# POVRotor.net
KiCad netlist of a schematic drawn in EAGLE
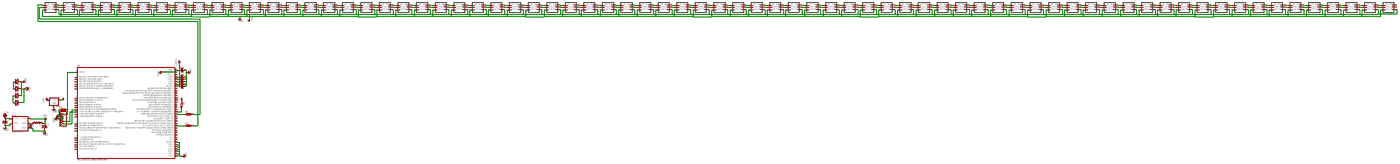
[diagram p0: schematic, sheet 1, overview]
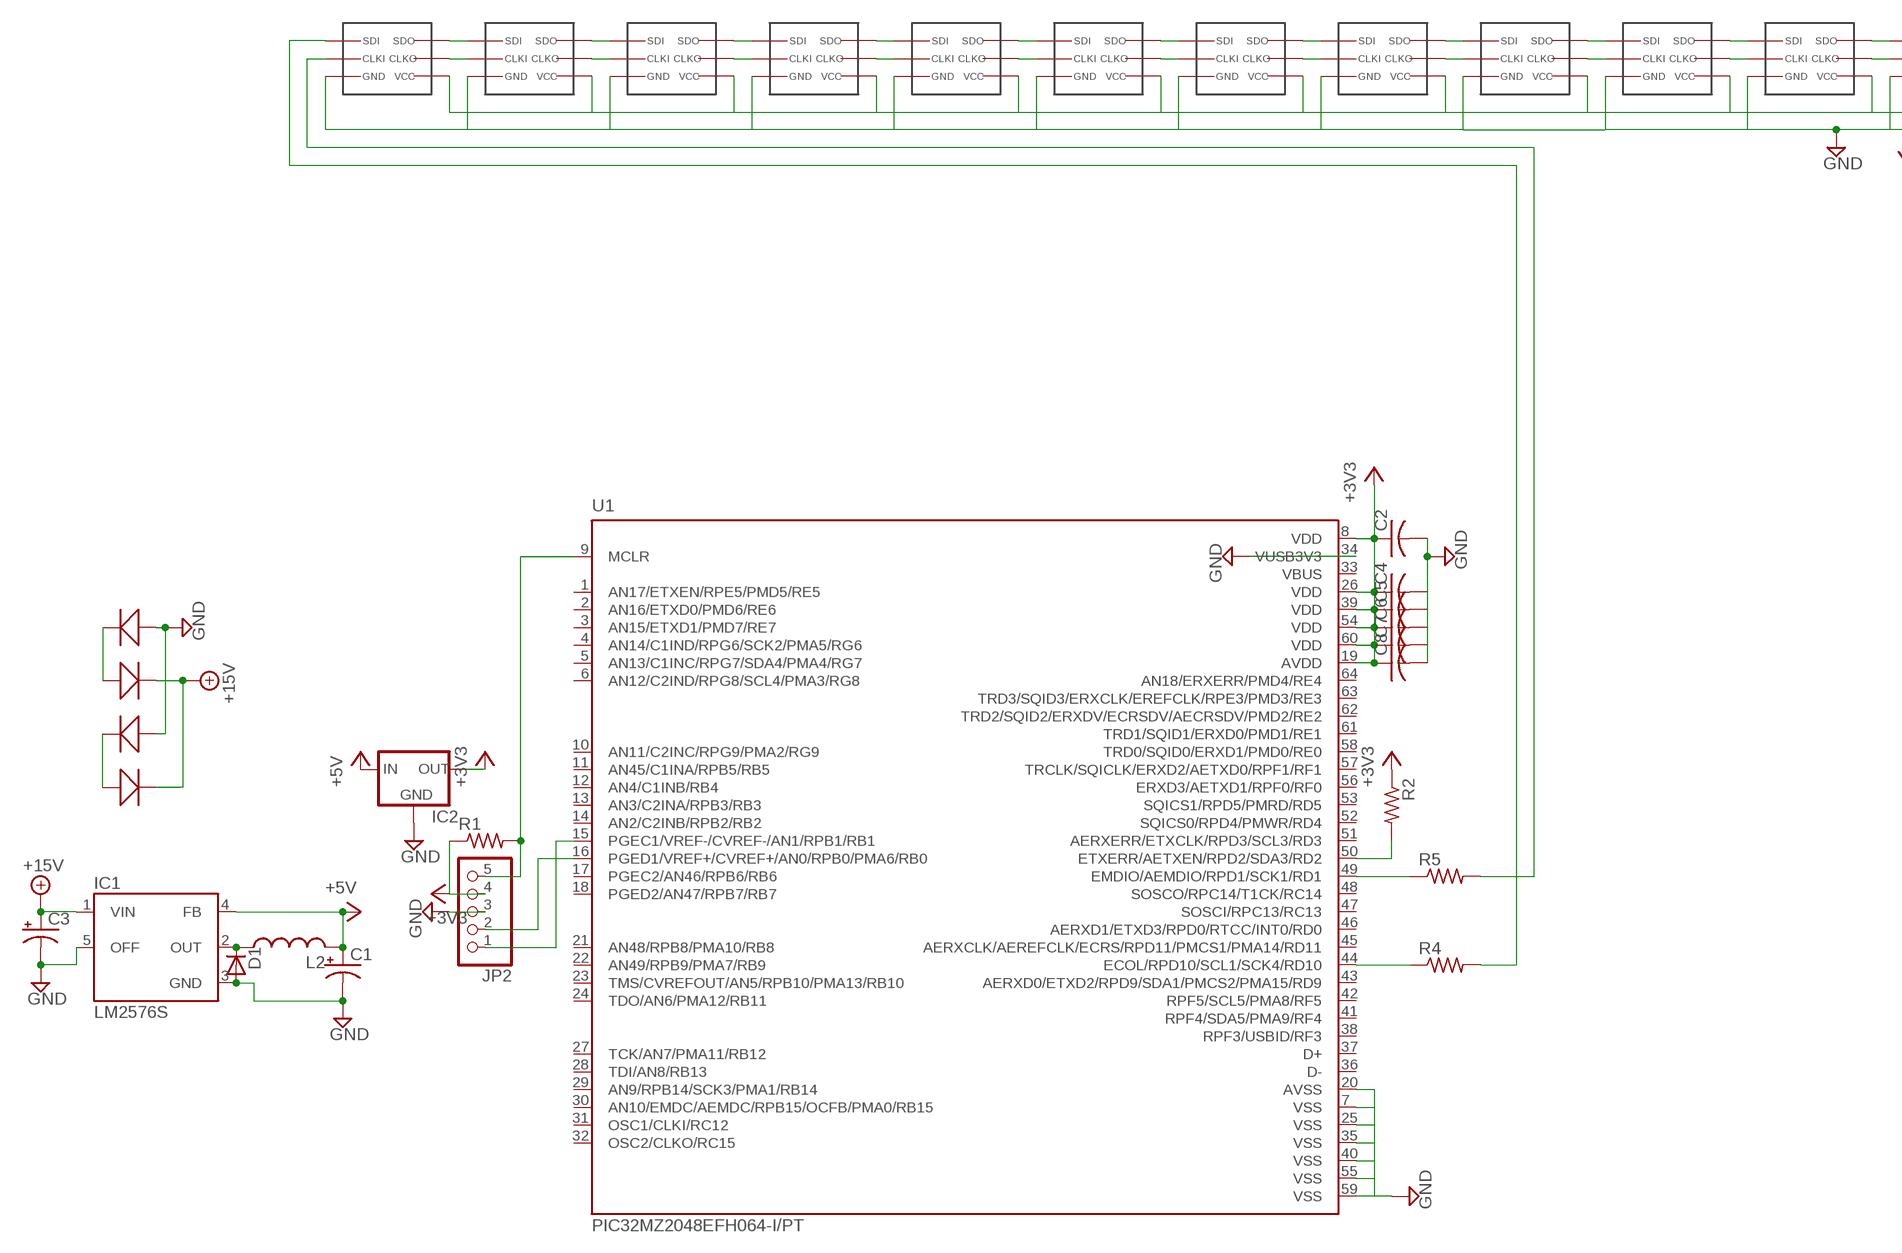
[diagram p1: schematic, sheet 1, part 1 of 8]
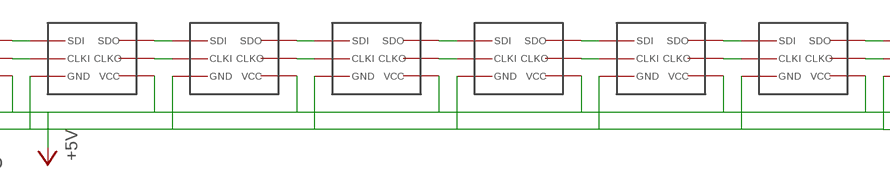
[diagram p2: schematic, sheet 1, part 2 of 8]
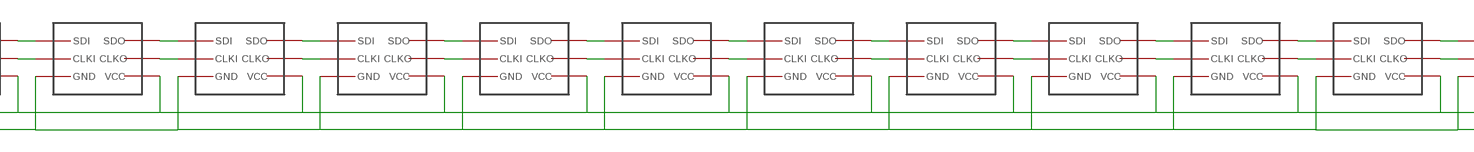
[diagram p3: schematic, sheet 1, part 3 of 8]
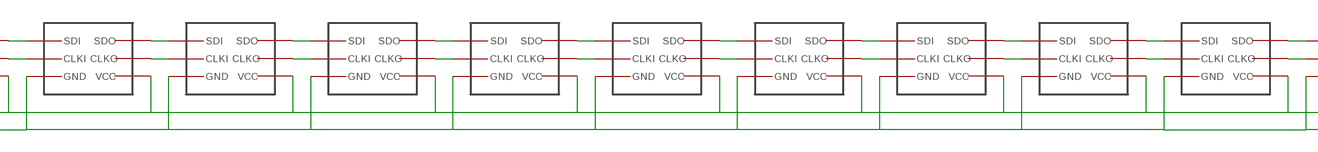
[diagram p4: schematic, sheet 1, part 4 of 8]
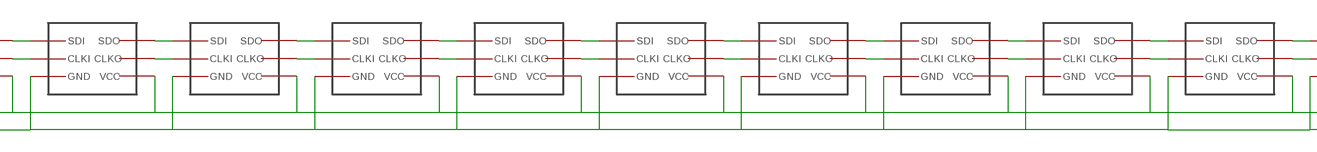
[diagram p5: schematic, sheet 1, part 5 of 8]
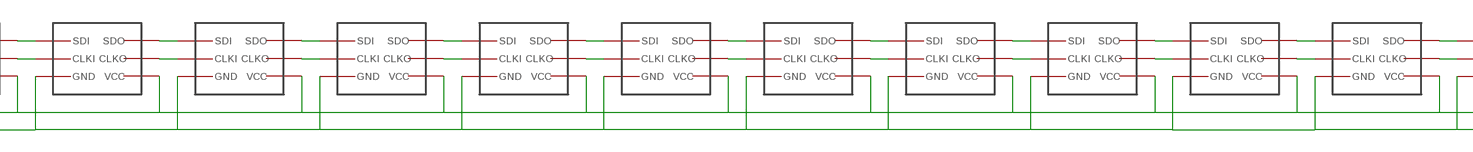
[diagram p6: schematic, sheet 1, part 6 of 8]
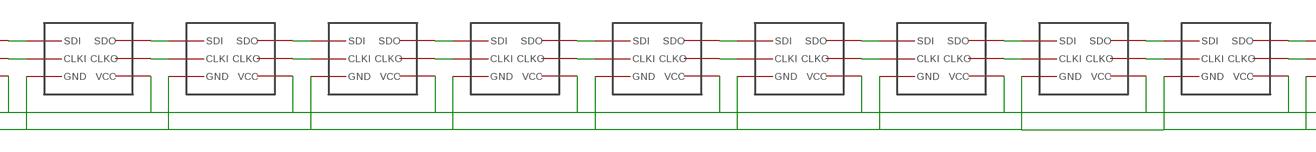
[diagram p7: schematic, sheet 1, part 7 of 8]
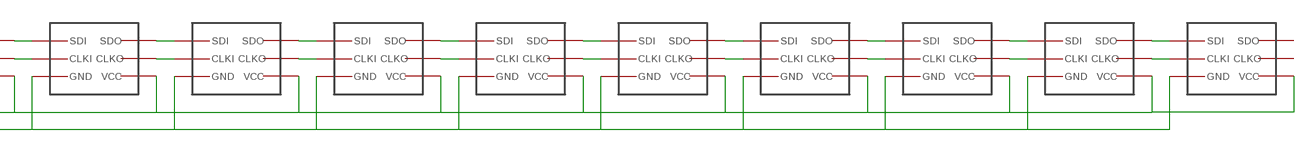
[diagram p8: schematic, sheet 1, part 8 of 8]

(export (version "E")
  (design (tool "Eeschema 10.0.6"))
  (components
    (comp (ref "C1")
      (value "CPOL-USE2,5-6E")
      (footprint "eagle-import:E2,5-6E")
      (libsource (lib "eagle-import") (part "CPOL-USE2,5-6E"))
    )
    (comp (ref "C2")
      (value "C-USC0805")
      (footprint "eagle-import:C0805")
      (libsource (lib "eagle-import") (part "C-USC0805"))
    )
    (comp (ref "C3")
      (value "CPOL-USE2,5-6E")
      (footprint "eagle-import:E2,5-6E")
      (libsource (lib "eagle-import") (part "CPOL-USE2,5-6E"))
    )
    (comp (ref "C4")
      (value "C-USC0805")
      (footprint "eagle-import:C0805")
      (libsource (lib "eagle-import") (part "C-USC0805"))
    )
    (comp (ref "C5")
      (value "C-USC0805")
      (footprint "eagle-import:C0805")
      (libsource (lib "eagle-import") (part "C-USC0805"))
    )
    (comp (ref "C6")
      (value "C-USC0805")
      (footprint "eagle-import:C0805")
      (libsource (lib "eagle-import") (part "C-USC0805"))
    )
    (comp (ref "C7")
      (value "C-USC0805")
      (footprint "eagle-import:C0805")
      (libsource (lib "eagle-import") (part "C-USC0805"))
    )
    (comp (ref "C8")
      (value "C-USC0805")
      (footprint "eagle-import:C0805")
      (libsource (lib "eagle-import") (part "C-USC0805"))
    )
    (comp (ref "D1")
      (value "BYS10")
      (footprint "eagle-import:SOD106A")
      (fields (field (name "MPN") "BYS10/45"))
      (libsource (lib "eagle-import") (part "BYS10"))
    )
    (comp (ref "D2")
      (value "SMD-DIODE-SCHOTTKY-40V-3A(DO-214AB)")
      (footprint "eagle-import:DO-214AB")
      (fields (field (name "MF") "Vishay") (field (name "MP") "SS34-E3/57T"))
      (libsource (lib "eagle-import") (part "SMD-DIODE-SCHOTTKY-40V-3A(DO-214AB)"))
    )
    (comp (ref "D3")
      (value "SMD-DIODE-SCHOTTKY-40V-3A(DO-214AB)")
      (footprint "eagle-import:DO-214AB")
      (fields (field (name "MF") "Vishay") (field (name "MP") "SS34-E3/57T"))
      (libsource (lib "eagle-import") (part "SMD-DIODE-SCHOTTKY-40V-3A(DO-214AB)"))
    )
    (comp (ref "D4")
      (value "SMD-DIODE-SCHOTTKY-40V-3A(DO-214AB)")
      (footprint "eagle-import:DO-214AB")
      (fields (field (name "MF") "Vishay") (field (name "MP") "SS34-E3/57T"))
      (libsource (lib "eagle-import") (part "SMD-DIODE-SCHOTTKY-40V-3A(DO-214AB)"))
    )
    (comp (ref "D5")
      (value "SMD-DIODE-SCHOTTKY-40V-3A(DO-214AB)")
      (footprint "eagle-import:DO-214AB")
      (fields (field (name "MF") "Vishay") (field (name "MP") "SS34-E3/57T"))
      (libsource (lib "eagle-import") (part "SMD-DIODE-SCHOTTKY-40V-3A(DO-214AB)"))
    )
    (comp (ref "IC1")
      (value "LM2576S")
      (footprint "eagle-import:TO263-5")
      (libsource (lib "eagle-import") (part "LM2576S"))
    )
    (comp (ref "IC2")
      (value "LM1117")
      (footprint "eagle-import:SOT223")
      (libsource (lib "eagle-import") (part "LM1117"))
    )
    (comp (ref "JP2")
      (value "PINHD-1X5")
      (footprint "eagle-import:1X05")
      (libsource (lib "eagle-import") (part "PINHD-1X5"))
    )
    (comp (ref "L2")
      (value "L-USL4532P")
      (footprint "eagle-import:L4532P")
      (libsource (lib "eagle-import") (part "L-USL4532P"))
    )
    (comp (ref "R1")
      (value "R-US_R0805")
      (footprint "eagle-import:R0805")
      (libsource (lib "eagle-import") (part "R-US_R0805"))
    )
    (comp (ref "R2")
      (value "R-US_R0603")
      (footprint "eagle-import:R0603")
      (libsource (lib "eagle-import") (part "R-US_R0603"))
    )
    (comp (ref "R4")
      (value "R-US_R0603")
      (footprint "eagle-import:R0603")
      (libsource (lib "eagle-import") (part "R-US_R0603"))
    )
    (comp (ref "R5")
      (value "R-US_R0603")
      (footprint "eagle-import:R0603")
      (libsource (lib "eagle-import") (part "R-US_R0603"))
    )
    (comp (ref "U$1")
      (value "2020LED")
      (footprint "eagle-import:2020LED")
      (libsource (lib "eagle-import") (part "2020LED"))
    )
    (comp (ref "U$2")
      (value "2020LED")
      (footprint "eagle-import:2020LED")
      (libsource (lib "eagle-import") (part "2020LED"))
    )
    (comp (ref "U$3")
      (value "2020LED")
      (footprint "eagle-import:2020LED")
      (libsource (lib "eagle-import") (part "2020LED"))
    )
    (comp (ref "U$4")
      (value "2020LED")
      (footprint "eagle-import:2020LED")
      (libsource (lib "eagle-import") (part "2020LED"))
    )
    (comp (ref "U$5")
      (value "2020LED")
      (footprint "eagle-import:2020LED")
      (libsource (lib "eagle-import") (part "2020LED"))
    )
    (comp (ref "U$6")
      (value "2020LED")
      (footprint "eagle-import:2020LED")
      (libsource (lib "eagle-import") (part "2020LED"))
    )
    (comp (ref "U$7")
      (value "2020LED")
      (footprint "eagle-import:2020LED")
      (libsource (lib "eagle-import") (part "2020LED"))
    )
    (comp (ref "U$8")
      (value "2020LED")
      (footprint "eagle-import:2020LED")
      (libsource (lib "eagle-import") (part "2020LED"))
    )
    (comp (ref "U$9")
      (value "2020LED")
      (footprint "eagle-import:2020LED")
      (libsource (lib "eagle-import") (part "2020LED"))
    )
    (comp (ref "U$10")
      (value "2020LED")
      (footprint "eagle-import:2020LED")
      (libsource (lib "eagle-import") (part "2020LED"))
    )
    (comp (ref "U$11")
      (value "2020LED")
      (footprint "eagle-import:2020LED")
      (libsource (lib "eagle-import") (part "2020LED"))
    )
    (comp (ref "U$12")
      (value "2020LED")
      (footprint "eagle-import:2020LED")
      (libsource (lib "eagle-import") (part "2020LED"))
    )
    (comp (ref "U$13")
      (value "2020LED")
      (footprint "eagle-import:2020LED")
      (libsource (lib "eagle-import") (part "2020LED"))
    )
    (comp (ref "U$14")
      (value "2020LED")
      (footprint "eagle-import:2020LED")
      (libsource (lib "eagle-import") (part "2020LED"))
    )
    (comp (ref "U$15")
      (value "2020LED")
      (footprint "eagle-import:2020LED")
      (libsource (lib "eagle-import") (part "2020LED"))
    )
    (comp (ref "U$16")
      (value "2020LED")
      (footprint "eagle-import:2020LED")
      (libsource (lib "eagle-import") (part "2020LED"))
    )
    (comp (ref "U$17")
      (value "2020LED")
      (footprint "eagle-import:2020LED")
      (libsource (lib "eagle-import") (part "2020LED"))
    )
    (comp (ref "U$18")
      (value "2020LED")
      (footprint "eagle-import:2020LED")
      (libsource (lib "eagle-import") (part "2020LED"))
    )
    (comp (ref "U$19")
      (value "2020LED")
      (footprint "eagle-import:2020LED")
      (libsource (lib "eagle-import") (part "2020LED"))
    )
    (comp (ref "U$20")
      (value "2020LED")
      (footprint "eagle-import:2020LED")
      (libsource (lib "eagle-import") (part "2020LED"))
    )
    (comp (ref "U$21")
      (value "2020LED")
      (footprint "eagle-import:2020LED")
      (libsource (lib "eagle-import") (part "2020LED"))
    )
    (comp (ref "U$22")
      (value "2020LED")
      (footprint "eagle-import:2020LED")
      (libsource (lib "eagle-import") (part "2020LED"))
    )
    (comp (ref "U$23")
      (value "2020LED")
      (footprint "eagle-import:2020LED")
      (libsource (lib "eagle-import") (part "2020LED"))
    )
    (comp (ref "U$24")
      (value "2020LED")
      (footprint "eagle-import:2020LED")
      (libsource (lib "eagle-import") (part "2020LED"))
    )
    (comp (ref "U$25")
      (value "2020LED")
      (footprint "eagle-import:2020LED")
      (libsource (lib "eagle-import") (part "2020LED"))
    )
    (comp (ref "U$26")
      (value "2020LED")
      (footprint "eagle-import:2020LED")
      (libsource (lib "eagle-import") (part "2020LED"))
    )
    (comp (ref "U$27")
      (value "2020LED")
      (footprint "eagle-import:2020LED")
      (libsource (lib "eagle-import") (part "2020LED"))
    )
    (comp (ref "U$28")
      (value "2020LED")
      (footprint "eagle-import:2020LED")
      (libsource (lib "eagle-import") (part "2020LED"))
    )
    (comp (ref "U$29")
      (value "2020LED")
      (footprint "eagle-import:2020LED")
      (libsource (lib "eagle-import") (part "2020LED"))
    )
    (comp (ref "U$30")
      (value "2020LED")
      (footprint "eagle-import:2020LED")
      (libsource (lib "eagle-import") (part "2020LED"))
    )
    (comp (ref "U$31")
      (value "2020LED")
      (footprint "eagle-import:2020LED")
      (libsource (lib "eagle-import") (part "2020LED"))
    )
    (comp (ref "U$32")
      (value "2020LED")
      (footprint "eagle-import:2020LED")
      (libsource (lib "eagle-import") (part "2020LED"))
    )
    (comp (ref "U$33")
      (value "2020LED")
      (footprint "eagle-import:2020LED")
      (libsource (lib "eagle-import") (part "2020LED"))
    )
    (comp (ref "U$34")
      (value "2020LED")
      (footprint "eagle-import:2020LED")
      (libsource (lib "eagle-import") (part "2020LED"))
    )
    (comp (ref "U$35")
      (value "2020LED")
      (footprint "eagle-import:2020LED")
      (libsource (lib "eagle-import") (part "2020LED"))
    )
    (comp (ref "U$36")
      (value "2020LED")
      (footprint "eagle-import:2020LED")
      (libsource (lib "eagle-import") (part "2020LED"))
    )
    (comp (ref "U$37")
      (value "2020LED")
      (footprint "eagle-import:2020LED")
      (libsource (lib "eagle-import") (part "2020LED"))
    )
    (comp (ref "U$38")
      (value "2020LED")
      (footprint "eagle-import:2020LED")
      (libsource (lib "eagle-import") (part "2020LED"))
    )
    (comp (ref "U$39")
      (value "2020LED")
      (footprint "eagle-import:2020LED")
      (libsource (lib "eagle-import") (part "2020LED"))
    )
    (comp (ref "U$40")
      (value "2020LED")
      (footprint "eagle-import:2020LED")
      (libsource (lib "eagle-import") (part "2020LED"))
    )
    (comp (ref "U$41")
      (value "2020LED")
      (footprint "eagle-import:2020LED")
      (libsource (lib "eagle-import") (part "2020LED"))
    )
    (comp (ref "U$42")
      (value "2020LED")
      (footprint "eagle-import:2020LED")
      (libsource (lib "eagle-import") (part "2020LED"))
    )
    (comp (ref "U$43")
      (value "2020LED")
      (footprint "eagle-import:2020LED")
      (libsource (lib "eagle-import") (part "2020LED"))
    )
    (comp (ref "U$44")
      (value "2020LED")
      (footprint "eagle-import:2020LED")
      (libsource (lib "eagle-import") (part "2020LED"))
    )
    (comp (ref "U$45")
      (value "2020LED")
      (footprint "eagle-import:2020LED")
      (libsource (lib "eagle-import") (part "2020LED"))
    )
    (comp (ref "U$46")
      (value "2020LED")
      (footprint "eagle-import:2020LED")
      (libsource (lib "eagle-import") (part "2020LED"))
    )
    (comp (ref "U$47")
      (value "2020LED")
      (footprint "eagle-import:2020LED")
      (libsource (lib "eagle-import") (part "2020LED"))
    )
    (comp (ref "U$48")
      (value "2020LED")
      (footprint "eagle-import:2020LED")
      (libsource (lib "eagle-import") (part "2020LED"))
    )
    (comp (ref "U$49")
      (value "2020LED")
      (footprint "eagle-import:2020LED")
      (libsource (lib "eagle-import") (part "2020LED"))
    )
    (comp (ref "U$50")
      (value "2020LED")
      (footprint "eagle-import:2020LED")
      (libsource (lib "eagle-import") (part "2020LED"))
    )
    (comp (ref "U$51")
      (value "2020LED")
      (footprint "eagle-import:2020LED")
      (libsource (lib "eagle-import") (part "2020LED"))
    )
    (comp (ref "U$52")
      (value "2020LED")
      (footprint "eagle-import:2020LED")
      (libsource (lib "eagle-import") (part "2020LED"))
    )
    (comp (ref "U$53")
      (value "2020LED")
      (footprint "eagle-import:2020LED")
      (libsource (lib "eagle-import") (part "2020LED"))
    )
    (comp (ref "U$54")
      (value "2020LED")
      (footprint "eagle-import:2020LED")
      (libsource (lib "eagle-import") (part "2020LED"))
    )
    (comp (ref "U$55")
      (value "2020LED")
      (footprint "eagle-import:2020LED")
      (libsource (lib "eagle-import") (part "2020LED"))
    )
    (comp (ref "U$56")
      (value "2020LED")
      (footprint "eagle-import:2020LED")
      (libsource (lib "eagle-import") (part "2020LED"))
    )
    (comp (ref "U$57")
      (value "2020LED")
      (footprint "eagle-import:2020LED")
      (libsource (lib "eagle-import") (part "2020LED"))
    )
    (comp (ref "U$58")
      (value "2020LED")
      (footprint "eagle-import:2020LED")
      (libsource (lib "eagle-import") (part "2020LED"))
    )
    (comp (ref "U$59")
      (value "2020LED")
      (footprint "eagle-import:2020LED")
      (libsource (lib "eagle-import") (part "2020LED"))
    )
    (comp (ref "U$60")
      (value "2020LED")
      (footprint "eagle-import:2020LED")
      (libsource (lib "eagle-import") (part "2020LED"))
    )
    (comp (ref "U$61")
      (value "2020LED")
      (footprint "eagle-import:2020LED")
      (libsource (lib "eagle-import") (part "2020LED"))
    )
    (comp (ref "U$62")
      (value "2020LED")
      (footprint "eagle-import:2020LED")
      (libsource (lib "eagle-import") (part "2020LED"))
    )
    (comp (ref "U$63")
      (value "2020LED")
      (footprint "eagle-import:2020LED")
      (libsource (lib "eagle-import") (part "2020LED"))
    )
    (comp (ref "U$64")
      (value "2020LED")
      (footprint "eagle-import:2020LED")
      (libsource (lib "eagle-import") (part "2020LED"))
    )
    (comp (ref "U$65")
      (value "2020LED")
      (footprint "eagle-import:2020LED")
      (libsource (lib "eagle-import") (part "2020LED"))
    )
    (comp (ref "U$66")
      (value "2020LED")
      (footprint "eagle-import:2020LED")
      (libsource (lib "eagle-import") (part "2020LED"))
    )
    (comp (ref "U$67")
      (value "2020LED")
      (footprint "eagle-import:2020LED")
      (libsource (lib "eagle-import") (part "2020LED"))
    )
    (comp (ref "U$68")
      (value "2020LED")
      (footprint "eagle-import:2020LED")
      (libsource (lib "eagle-import") (part "2020LED"))
    )
    (comp (ref "U$69")
      (value "2020LED")
      (footprint "eagle-import:2020LED")
      (libsource (lib "eagle-import") (part "2020LED"))
    )
    (comp (ref "U$70")
      (value "2020LED")
      (footprint "eagle-import:2020LED")
      (libsource (lib "eagle-import") (part "2020LED"))
    )
    (comp (ref "U$71")
      (value "2020LED")
      (footprint "eagle-import:2020LED")
      (libsource (lib "eagle-import") (part "2020LED"))
    )
    (comp (ref "U$72")
      (value "2020LED")
      (footprint "eagle-import:2020LED")
      (libsource (lib "eagle-import") (part "2020LED"))
    )
    (comp (ref "U$73")
      (value "2020LED")
      (footprint "eagle-import:2020LED")
      (libsource (lib "eagle-import") (part "2020LED"))
    )
    (comp (ref "U1")
      (value "PIC32MZ2048EFH064-I/PT")
      (footprint "eagle-import:QFP50P1200X1200X120-64N")
      (fields (field (name "MF") "Microchip"))
      (libsource (lib "eagle-import") (part "PIC32MZ2048EFH064-I/PT"))
    )
  )
  (nets
    (net (code "1") (name "+3V3") (class "Default")
      (node (ref "C2") (pin "1") (pinfunction "1_1") (pintype "passive"))
      (node (ref "C4") (pin "1") (pinfunction "1_1") (pintype "passive"))
      (node (ref "C5") (pin "1") (pinfunction "1_1") (pintype "passive"))
      (node (ref "C6") (pin "1") (pinfunction "1_1") (pintype "passive"))
      (node (ref "C7") (pin "1") (pinfunction "1_1") (pintype "passive"))
      (node (ref "C8") (pin "1") (pinfunction "1_1") (pintype "passive"))
      (node (ref "IC2") (pin "2") (pinfunction "OUT_2") (pintype "passive"))
      (node (ref "JP2") (pin "4") (pinfunction "4_4") (pintype "passive"))
      (node (ref "R1") (pin "1") (pinfunction "1_1") (pintype "passive"))
      (node (ref "R2") (pin "1") (pinfunction "1_1") (pintype "passive"))
      (node (ref "U1") (pin "19") (pinfunction "AVDD_19") (pintype "power_in"))
      (node (ref "U1") (pin "26") (pinfunction "VDD_26") (pintype "power_in"))
      (node (ref "U1") (pin "39") (pinfunction "VDD_39") (pintype "power_in"))
      (node (ref "U1") (pin "54") (pinfunction "VDD_54") (pintype "power_in"))
      (node (ref "U1") (pin "60") (pinfunction "VDD_60") (pintype "power_in"))
      (node (ref "U1") (pin "8") (pinfunction "VDD_8") (pintype "power_in"))
    )
    (net (code "2") (name "+5V") (class "Default")
      (node (ref "C1") (pin "+") (pinfunction "+_+") (pintype "passive"))
      (node (ref "IC1") (pin "4") (pinfunction "FB_4") (pintype "input"))
      (node (ref "IC2") (pin "3") (pinfunction "IN_3") (pintype "input"))
      (node (ref "L2") (pin "2") (pinfunction "2_2") (pintype "passive"))
      (node (ref "U$1") (pin "VCC") (pinfunction "VCC_VCC") (pintype "bidirectional"))
      (node (ref "U$10") (pin "VCC") (pinfunction "VCC_VCC") (pintype "bidirectional"))
      (node (ref "U$11") (pin "VCC") (pinfunction "VCC_VCC") (pintype "bidirectional"))
      (node (ref "U$12") (pin "VCC") (pinfunction "VCC_VCC") (pintype "bidirectional"))
      (node (ref "U$13") (pin "VCC") (pinfunction "VCC_VCC") (pintype "bidirectional"))
      (node (ref "U$14") (pin "VCC") (pinfunction "VCC_VCC") (pintype "bidirectional"))
      (node (ref "U$15") (pin "VCC") (pinfunction "VCC_VCC") (pintype "bidirectional"))
      (node (ref "U$16") (pin "VCC") (pinfunction "VCC_VCC") (pintype "bidirectional"))
      (node (ref "U$17") (pin "VCC") (pinfunction "VCC_VCC") (pintype "bidirectional"))
      (node (ref "U$18") (pin "VCC") (pinfunction "VCC_VCC") (pintype "bidirectional"))
      (node (ref "U$19") (pin "VCC") (pinfunction "VCC_VCC") (pintype "bidirectional"))
      (node (ref "U$2") (pin "VCC") (pinfunction "VCC_VCC") (pintype "bidirectional"))
      (node (ref "U$20") (pin "VCC") (pinfunction "VCC_VCC") (pintype "bidirectional"))
      (node (ref "U$21") (pin "VCC") (pinfunction "VCC_VCC") (pintype "bidirectional"))
      (node (ref "U$22") (pin "VCC") (pinfunction "VCC_VCC") (pintype "bidirectional"))
      (node (ref "U$23") (pin "VCC") (pinfunction "VCC_VCC") (pintype "bidirectional"))
      (node (ref "U$24") (pin "VCC") (pinfunction "VCC_VCC") (pintype "bidirectional"))
      (node (ref "U$25") (pin "VCC") (pinfunction "VCC_VCC") (pintype "bidirectional"))
      (node (ref "U$26") (pin "VCC") (pinfunction "VCC_VCC") (pintype "bidirectional"))
      (node (ref "U$27") (pin "VCC") (pinfunction "VCC_VCC") (pintype "bidirectional"))
      (node (ref "U$28") (pin "VCC") (pinfunction "VCC_VCC") (pintype "bidirectional"))
      (node (ref "U$29") (pin "VCC") (pinfunction "VCC_VCC") (pintype "bidirectional"))
      (node (ref "U$3") (pin "VCC") (pinfunction "VCC_VCC") (pintype "bidirectional"))
      (node (ref "U$30") (pin "VCC") (pinfunction "VCC_VCC") (pintype "bidirectional"))
      (node (ref "U$31") (pin "VCC") (pinfunction "VCC_VCC") (pintype "bidirectional"))
      (node (ref "U$32") (pin "VCC") (pinfunction "VCC_VCC") (pintype "bidirectional"))
      (node (ref "U$33") (pin "VCC") (pinfunction "VCC_VCC") (pintype "bidirectional"))
      (node (ref "U$34") (pin "VCC") (pinfunction "VCC_VCC") (pintype "bidirectional"))
      (node (ref "U$35") (pin "VCC") (pinfunction "VCC_VCC") (pintype "bidirectional"))
      (node (ref "U$36") (pin "VCC") (pinfunction "VCC_VCC") (pintype "bidirectional"))
      (node (ref "U$37") (pin "VCC") (pinfunction "VCC_VCC") (pintype "bidirectional"))
      (node (ref "U$38") (pin "VCC") (pinfunction "VCC_VCC") (pintype "bidirectional"))
      (node (ref "U$39") (pin "VCC") (pinfunction "VCC_VCC") (pintype "bidirectional"))
      (node (ref "U$4") (pin "VCC") (pinfunction "VCC_VCC") (pintype "bidirectional"))
      (node (ref "U$40") (pin "VCC") (pinfunction "VCC_VCC") (pintype "bidirectional"))
      (node (ref "U$41") (pin "VCC") (pinfunction "VCC_VCC") (pintype "bidirectional"))
      (node (ref "U$42") (pin "VCC") (pinfunction "VCC_VCC") (pintype "bidirectional"))
      (node (ref "U$43") (pin "VCC") (pinfunction "VCC_VCC") (pintype "bidirectional"))
      (node (ref "U$44") (pin "VCC") (pinfunction "VCC_VCC") (pintype "bidirectional"))
      (node (ref "U$45") (pin "VCC") (pinfunction "VCC_VCC") (pintype "bidirectional"))
      (node (ref "U$46") (pin "VCC") (pinfunction "VCC_VCC") (pintype "bidirectional"))
      (node (ref "U$47") (pin "VCC") (pinfunction "VCC_VCC") (pintype "bidirectional"))
      (node (ref "U$48") (pin "VCC") (pinfunction "VCC_VCC") (pintype "bidirectional"))
      (node (ref "U$49") (pin "VCC") (pinfunction "VCC_VCC") (pintype "bidirectional"))
      (node (ref "U$5") (pin "VCC") (pinfunction "VCC_VCC") (pintype "bidirectional"))
      (node (ref "U$50") (pin "VCC") (pinfunction "VCC_VCC") (pintype "bidirectional"))
      (node (ref "U$51") (pin "VCC") (pinfunction "VCC_VCC") (pintype "bidirectional"))
      (node (ref "U$52") (pin "VCC") (pinfunction "VCC_VCC") (pintype "bidirectional"))
      (node (ref "U$53") (pin "VCC") (pinfunction "VCC_VCC") (pintype "bidirectional"))
      (node (ref "U$54") (pin "VCC") (pinfunction "VCC_VCC") (pintype "bidirectional"))
      (node (ref "U$55") (pin "VCC") (pinfunction "VCC_VCC") (pintype "bidirectional"))
      (node (ref "U$56") (pin "VCC") (pinfunction "VCC_VCC") (pintype "bidirectional"))
      (node (ref "U$57") (pin "VCC") (pinfunction "VCC_VCC") (pintype "bidirectional"))
      (node (ref "U$58") (pin "VCC") (pinfunction "VCC_VCC") (pintype "bidirectional"))
      (node (ref "U$59") (pin "VCC") (pinfunction "VCC_VCC") (pintype "bidirectional"))
      (node (ref "U$6") (pin "VCC") (pinfunction "VCC_VCC") (pintype "bidirectional"))
      (node (ref "U$60") (pin "VCC") (pinfunction "VCC_VCC") (pintype "bidirectional"))
      (node (ref "U$61") (pin "VCC") (pinfunction "VCC_VCC") (pintype "bidirectional"))
      (node (ref "U$62") (pin "VCC") (pinfunction "VCC_VCC") (pintype "bidirectional"))
      (node (ref "U$63") (pin "VCC") (pinfunction "VCC_VCC") (pintype "bidirectional"))
      (node (ref "U$64") (pin "VCC") (pinfunction "VCC_VCC") (pintype "bidirectional"))
      (node (ref "U$65") (pin "VCC") (pinfunction "VCC_VCC") (pintype "bidirectional"))
      (node (ref "U$66") (pin "VCC") (pinfunction "VCC_VCC") (pintype "bidirectional"))
      (node (ref "U$67") (pin "VCC") (pinfunction "VCC_VCC") (pintype "bidirectional"))
      (node (ref "U$68") (pin "VCC") (pinfunction "VCC_VCC") (pintype "bidirectional"))
      (node (ref "U$69") (pin "VCC") (pinfunction "VCC_VCC") (pintype "bidirectional"))
      (node (ref "U$7") (pin "VCC") (pinfunction "VCC_VCC") (pintype "bidirectional"))
      (node (ref "U$70") (pin "VCC") (pinfunction "VCC_VCC") (pintype "bidirectional"))
      (node (ref "U$71") (pin "VCC") (pinfunction "VCC_VCC") (pintype "bidirectional"))
      (node (ref "U$72") (pin "VCC") (pinfunction "VCC_VCC") (pintype "bidirectional"))
      (node (ref "U$73") (pin "VCC") (pinfunction "VCC_VCC") (pintype "bidirectional"))
      (node (ref "U$8") (pin "VCC") (pinfunction "VCC_VCC") (pintype "bidirectional"))
      (node (ref "U$9") (pin "VCC") (pinfunction "VCC_VCC") (pintype "bidirectional"))
    )
    (net (code "3") (name "+15V") (class "Default")
      (node (ref "C3") (pin "+") (pinfunction "+_+") (pintype "passive"))
      (node (ref "D2") (pin "2") (pinfunction "-_2") (pintype "passive"))
      (node (ref "D3") (pin "2") (pinfunction "-_2") (pintype "passive"))
      (node (ref "IC1") (pin "1") (pinfunction "VIN_1") (pintype "power_in"))
    )
    (net (code "4") (name "/VBUS") (class "Default")
      (node (ref "U1") (pin "33") (pinfunction "VBUS_33") (pintype "power_in"))
    )
    (net (code "5") (name "GND") (class "Default")
      (node (ref "C1") (pin "-") (pinfunction "-_-") (pintype "passive"))
      (node (ref "C2") (pin "2") (pinfunction "2_2") (pintype "passive"))
      (node (ref "C3") (pin "-") (pinfunction "-_-") (pintype "passive"))
      (node (ref "C4") (pin "2") (pinfunction "2_2") (pintype "passive"))
      (node (ref "C5") (pin "2") (pinfunction "2_2") (pintype "passive"))
      (node (ref "C6") (pin "2") (pinfunction "2_2") (pintype "passive"))
      (node (ref "C7") (pin "2") (pinfunction "2_2") (pintype "passive"))
      (node (ref "C8") (pin "2") (pinfunction "2_2") (pintype "passive"))
      (node (ref "D1") (pin "A") (pinfunction "A_A") (pintype "passive"))
      (node (ref "D4") (pin "1") (pinfunction "+_1") (pintype "passive"))
      (node (ref "D5") (pin "1") (pinfunction "+_1") (pintype "passive"))
      (node (ref "IC1") (pin "3") (pinfunction "GND_3") (pintype "power_in"))
      (node (ref "IC1") (pin "5") (pinfunction "OFF_5") (pintype "input"))
      (node (ref "IC2") (pin "1") (pinfunction "GND_1") (pintype "input"))
      (node (ref "JP2") (pin "3") (pinfunction "3_3") (pintype "passive"))
      (node (ref "U$1") (pin "GND") (pinfunction "GND_GND") (pintype "bidirectional"))
      (node (ref "U$10") (pin "GND") (pinfunction "GND_GND") (pintype "bidirectional"))
      (node (ref "U$11") (pin "GND") (pinfunction "GND_GND") (pintype "bidirectional"))
      (node (ref "U$12") (pin "GND") (pinfunction "GND_GND") (pintype "bidirectional"))
      (node (ref "U$13") (pin "GND") (pinfunction "GND_GND") (pintype "bidirectional"))
      (node (ref "U$14") (pin "GND") (pinfunction "GND_GND") (pintype "bidirectional"))
      (node (ref "U$15") (pin "GND") (pinfunction "GND_GND") (pintype "bidirectional"))
      (node (ref "U$16") (pin "GND") (pinfunction "GND_GND") (pintype "bidirectional"))
      (node (ref "U$17") (pin "GND") (pinfunction "GND_GND") (pintype "bidirectional"))
      (node (ref "U$18") (pin "GND") (pinfunction "GND_GND") (pintype "bidirectional"))
      (node (ref "U$19") (pin "GND") (pinfunction "GND_GND") (pintype "bidirectional"))
      (node (ref "U$2") (pin "GND") (pinfunction "GND_GND") (pintype "bidirectional"))
      (node (ref "U$20") (pin "GND") (pinfunction "GND_GND") (pintype "bidirectional"))
      (node (ref "U$21") (pin "GND") (pinfunction "GND_GND") (pintype "bidirectional"))
      (node (ref "U$22") (pin "GND") (pinfunction "GND_GND") (pintype "bidirectional"))
      (node (ref "U$23") (pin "GND") (pinfunction "GND_GND") (pintype "bidirectional"))
      (node (ref "U$24") (pin "GND") (pinfunction "GND_GND") (pintype "bidirectional"))
      (node (ref "U$25") (pin "GND") (pinfunction "GND_GND") (pintype "bidirectional"))
      (node (ref "U$26") (pin "GND") (pinfunction "GND_GND") (pintype "bidirectional"))
      (node (ref "U$27") (pin "GND") (pinfunction "GND_GND") (pintype "bidirectional"))
      (node (ref "U$28") (pin "GND") (pinfunction "GND_GND") (pintype "bidirectional"))
      (node (ref "U$29") (pin "GND") (pinfunction "GND_GND") (pintype "bidirectional"))
      (node (ref "U$3") (pin "GND") (pinfunction "GND_GND") (pintype "bidirectional"))
      (node (ref "U$30") (pin "GND") (pinfunction "GND_GND") (pintype "bidirectional"))
      (node (ref "U$31") (pin "GND") (pinfunction "GND_GND") (pintype "bidirectional"))
      (node (ref "U$32") (pin "GND") (pinfunction "GND_GND") (pintype "bidirectional"))
      (node (ref "U$33") (pin "GND") (pinfunction "GND_GND") (pintype "bidirectional"))
      (node (ref "U$34") (pin "GND") (pinfunction "GND_GND") (pintype "bidirectional"))
      (node (ref "U$35") (pin "GND") (pinfunction "GND_GND") (pintype "bidirectional"))
      (node (ref "U$36") (pin "GND") (pinfunction "GND_GND") (pintype "bidirectional"))
      (node (ref "U$37") (pin "GND") (pinfunction "GND_GND") (pintype "bidirectional"))
      (node (ref "U$38") (pin "GND") (pinfunction "GND_GND") (pintype "bidirectional"))
      (node (ref "U$39") (pin "GND") (pinfunction "GND_GND") (pintype "bidirectional"))
      (node (ref "U$4") (pin "GND") (pinfunction "GND_GND") (pintype "bidirectional"))
      (node (ref "U$40") (pin "GND") (pinfunction "GND_GND") (pintype "bidirectional"))
      (node (ref "U$41") (pin "GND") (pinfunction "GND_GND") (pintype "bidirectional"))
      (node (ref "U$42") (pin "GND") (pinfunction "GND_GND") (pintype "bidirectional"))
      (node (ref "U$43") (pin "GND") (pinfunction "GND_GND") (pintype "bidirectional"))
      (node (ref "U$44") (pin "GND") (pinfunction "GND_GND") (pintype "bidirectional"))
      (node (ref "U$45") (pin "GND") (pinfunction "GND_GND") (pintype "bidirectional"))
      (node (ref "U$46") (pin "GND") (pinfunction "GND_GND") (pintype "bidirectional"))
      (node (ref "U$47") (pin "GND") (pinfunction "GND_GND") (pintype "bidirectional"))
      (node (ref "U$48") (pin "GND") (pinfunction "GND_GND") (pintype "bidirectional"))
      (node (ref "U$49") (pin "GND") (pinfunction "GND_GND") (pintype "bidirectional"))
      (node (ref "U$5") (pin "GND") (pinfunction "GND_GND") (pintype "bidirectional"))
      (node (ref "U$50") (pin "GND") (pinfunction "GND_GND") (pintype "bidirectional"))
      (node (ref "U$51") (pin "GND") (pinfunction "GND_GND") (pintype "bidirectional"))
      (node (ref "U$52") (pin "GND") (pinfunction "GND_GND") (pintype "bidirectional"))
      (node (ref "U$53") (pin "GND") (pinfunction "GND_GND") (pintype "bidirectional"))
      (node (ref "U$54") (pin "GND") (pinfunction "GND_GND") (pintype "bidirectional"))
      (node (ref "U$55") (pin "GND") (pinfunction "GND_GND") (pintype "bidirectional"))
      (node (ref "U$56") (pin "GND") (pinfunction "GND_GND") (pintype "bidirectional"))
      (node (ref "U$57") (pin "GND") (pinfunction "GND_GND") (pintype "bidirectional"))
      (node (ref "U$58") (pin "GND") (pinfunction "GND_GND") (pintype "bidirectional"))
      (node (ref "U$59") (pin "GND") (pinfunction "GND_GND") (pintype "bidirectional"))
      (node (ref "U$6") (pin "GND") (pinfunction "GND_GND") (pintype "bidirectional"))
      (node (ref "U$60") (pin "GND") (pinfunction "GND_GND") (pintype "bidirectional"))
      (node (ref "U$61") (pin "GND") (pinfunction "GND_GND") (pintype "bidirectional"))
      (node (ref "U$62") (pin "GND") (pinfunction "GND_GND") (pintype "bidirectional"))
      (node (ref "U$63") (pin "GND") (pinfunction "GND_GND") (pintype "bidirectional"))
      (node (ref "U$64") (pin "GND") (pinfunction "GND_GND") (pintype "bidirectional"))
      (node (ref "U$65") (pin "GND") (pinfunction "GND_GND") (pintype "bidirectional"))
      (node (ref "U$66") (pin "GND") (pinfunction "GND_GND") (pintype "bidirectional"))
      (node (ref "U$67") (pin "GND") (pinfunction "GND_GND") (pintype "bidirectional"))
      (node (ref "U$68") (pin "GND") (pinfunction "GND_GND") (pintype "bidirectional"))
      (node (ref "U$69") (pin "GND") (pinfunction "GND_GND") (pintype "bidirectional"))
      (node (ref "U$7") (pin "GND") (pinfunction "GND_GND") (pintype "bidirectional"))
      (node (ref "U$70") (pin "GND") (pinfunction "GND_GND") (pintype "bidirectional"))
      (node (ref "U$71") (pin "GND") (pinfunction "GND_GND") (pintype "bidirectional"))
      (node (ref "U$72") (pin "GND") (pinfunction "GND_GND") (pintype "bidirectional"))
      (node (ref "U$73") (pin "GND") (pinfunction "GND_GND") (pintype "bidirectional"))
      (node (ref "U$8") (pin "GND") (pinfunction "GND_GND") (pintype "bidirectional"))
      (node (ref "U$9") (pin "GND") (pinfunction "GND_GND") (pintype "bidirectional"))
      (node (ref "U1") (pin "20") (pinfunction "AVSS_20") (pintype "power_in"))
      (node (ref "U1") (pin "25") (pinfunction "VSS_25") (pintype "power_in"))
      (node (ref "U1") (pin "34") (pinfunction "VUSB3V3_34") (pintype "power_in"))
      (node (ref "U1") (pin "35") (pinfunction "VSS_35") (pintype "power_in"))
      (node (ref "U1") (pin "40") (pinfunction "VSS_40") (pintype "power_in"))
      (node (ref "U1") (pin "55") (pinfunction "VSS_55") (pintype "power_in"))
      (node (ref "U1") (pin "59") (pinfunction "VSS_59") (pintype "power_in"))
      (node (ref "U1") (pin "7") (pinfunction "VSS_7") (pintype "power_in"))
    )
    (net (code "6") (name "Net-(D2-+)") (class "Default")
      (node (ref "D2") (pin "1") (pinfunction "+_1") (pintype "passive"))
      (node (ref "D5") (pin "2") (pinfunction "-_2") (pintype "passive"))
    )
    (net (code "7") (name "Net-(D3-+)") (class "Default")
      (node (ref "D3") (pin "1") (pinfunction "+_1") (pintype "passive"))
      (node (ref "D4") (pin "2") (pinfunction "-_2") (pintype "passive"))
    )
    (net (code "8") (name "Net-(IC1-OUT)") (class "Default")
      (node (ref "D1") (pin "K") (pinfunction "K_K") (pintype "passive"))
      (node (ref "IC1") (pin "2") (pinfunction "OUT_2") (pintype "output"))
      (node (ref "L2") (pin "1") (pinfunction "1_1") (pintype "passive"))
    )
    (net (code "9") (name "Net-(R4-Pad2)") (class "Default")
      (node (ref "R4") (pin "2") (pinfunction "2_2") (pintype "passive"))
      (node (ref "U$2") (pin "SDI") (pinfunction "SDI_SDI") (pintype "bidirectional"))
    )
    (net (code "10") (name "Net-(R5-Pad2)") (class "Default")
      (node (ref "R5") (pin "2") (pinfunction "2_2") (pintype "passive"))
      (node (ref "U$2") (pin "CLKI") (pinfunction "CLKI_CLKI") (pintype "bidirectional"))
    )
    (net (code "11") (name "Net-(U$1-PadCLKI)") (class "Default")
      (node (ref "U$1") (pin "CLKI") (pinfunction "CLKI_CLKI") (pintype "bidirectional"))
      (node (ref "U$2") (pin "CLKO") (pinfunction "CLKO_CLKO") (pintype "bidirectional"))
    )
    (net (code "12") (name "Net-(U$1-PadCLKO)") (class "Default")
      (node (ref "U$1") (pin "CLKO") (pinfunction "CLKO_CLKO") (pintype "bidirectional"))
      (node (ref "U$3") (pin "CLKI") (pinfunction "CLKI_CLKI") (pintype "bidirectional"))
    )
    (net (code "13") (name "Net-(U$1-PadSDI)") (class "Default")
      (node (ref "U$1") (pin "SDI") (pinfunction "SDI_SDI") (pintype "bidirectional"))
      (node (ref "U$2") (pin "SDO") (pinfunction "SDO_SDO") (pintype "bidirectional"))
    )
    (net (code "14") (name "Net-(U$1-PadSDO)") (class "Default")
      (node (ref "U$1") (pin "SDO") (pinfunction "SDO_SDO") (pintype "bidirectional"))
      (node (ref "U$3") (pin "SDI") (pinfunction "SDI_SDI") (pintype "bidirectional"))
    )
    (net (code "15") (name "Net-(U$3-PadCLKO)") (class "Default")
      (node (ref "U$3") (pin "CLKO") (pinfunction "CLKO_CLKO") (pintype "bidirectional"))
      (node (ref "U$4") (pin "CLKI") (pinfunction "CLKI_CLKI") (pintype "bidirectional"))
    )
    (net (code "16") (name "Net-(U$3-PadSDO)") (class "Default")
      (node (ref "U$3") (pin "SDO") (pinfunction "SDO_SDO") (pintype "bidirectional"))
      (node (ref "U$4") (pin "SDI") (pinfunction "SDI_SDI") (pintype "bidirectional"))
    )
    (net (code "17") (name "Net-(U$4-PadCLKO)") (class "Default")
      (node (ref "U$4") (pin "CLKO") (pinfunction "CLKO_CLKO") (pintype "bidirectional"))
      (node (ref "U$5") (pin "CLKI") (pinfunction "CLKI_CLKI") (pintype "bidirectional"))
    )
    (net (code "18") (name "Net-(U$4-PadSDO)") (class "Default")
      (node (ref "U$4") (pin "SDO") (pinfunction "SDO_SDO") (pintype "bidirectional"))
      (node (ref "U$5") (pin "SDI") (pinfunction "SDI_SDI") (pintype "bidirectional"))
    )
    (net (code "19") (name "Net-(U$5-PadCLKO)") (class "Default")
      (node (ref "U$5") (pin "CLKO") (pinfunction "CLKO_CLKO") (pintype "bidirectional"))
      (node (ref "U$6") (pin "CLKI") (pinfunction "CLKI_CLKI") (pintype "bidirectional"))
    )
    (net (code "20") (name "Net-(U$5-PadSDO)") (class "Default")
      (node (ref "U$5") (pin "SDO") (pinfunction "SDO_SDO") (pintype "bidirectional"))
      (node (ref "U$6") (pin "SDI") (pinfunction "SDI_SDI") (pintype "bidirectional"))
    )
    (net (code "21") (name "Net-(U$6-PadCLKO)") (class "Default")
      (node (ref "U$6") (pin "CLKO") (pinfunction "CLKO_CLKO") (pintype "bidirectional"))
      (node (ref "U$7") (pin "CLKI") (pinfunction "CLKI_CLKI") (pintype "bidirectional"))
    )
    (net (code "22") (name "Net-(U$6-PadSDO)") (class "Default")
      (node (ref "U$6") (pin "SDO") (pinfunction "SDO_SDO") (pintype "bidirectional"))
      (node (ref "U$7") (pin "SDI") (pinfunction "SDI_SDI") (pintype "bidirectional"))
    )
    (net (code "23") (name "Net-(U$7-PadCLKO)") (class "Default")
      (node (ref "U$7") (pin "CLKO") (pinfunction "CLKO_CLKO") (pintype "bidirectional"))
      (node (ref "U$8") (pin "CLKI") (pinfunction "CLKI_CLKI") (pintype "bidirectional"))
    )
    (net (code "24") (name "Net-(U$7-PadSDO)") (class "Default")
      (node (ref "U$7") (pin "SDO") (pinfunction "SDO_SDO") (pintype "bidirectional"))
      (node (ref "U$8") (pin "SDI") (pinfunction "SDI_SDI") (pintype "bidirectional"))
    )
    (net (code "25") (name "Net-(U$8-PadCLKO)") (class "Default")
      (node (ref "U$8") (pin "CLKO") (pinfunction "CLKO_CLKO") (pintype "bidirectional"))
      (node (ref "U$9") (pin "CLKI") (pinfunction "CLKI_CLKI") (pintype "bidirectional"))
    )
    (net (code "26") (name "Net-(U$8-PadSDO)") (class "Default")
      (node (ref "U$8") (pin "SDO") (pinfunction "SDO_SDO") (pintype "bidirectional"))
      (node (ref "U$9") (pin "SDI") (pinfunction "SDI_SDI") (pintype "bidirectional"))
    )
    (net (code "27") (name "Net-(U$10-PadCLKI)") (class "Default")
      (node (ref "U$10") (pin "CLKI") (pinfunction "CLKI_CLKI") (pintype "bidirectional"))
      (node (ref "U$9") (pin "CLKO") (pinfunction "CLKO_CLKO") (pintype "bidirectional"))
    )
    (net (code "28") (name "Net-(U$10-PadCLKO)") (class "Default")
      (node (ref "U$10") (pin "CLKO") (pinfunction "CLKO_CLKO") (pintype "bidirectional"))
      (node (ref "U$11") (pin "CLKI") (pinfunction "CLKI_CLKI") (pintype "bidirectional"))
    )
    (net (code "29") (name "Net-(U$10-PadSDI)") (class "Default")
      (node (ref "U$10") (pin "SDI") (pinfunction "SDI_SDI") (pintype "bidirectional"))
      (node (ref "U$9") (pin "SDO") (pinfunction "SDO_SDO") (pintype "bidirectional"))
    )
    (net (code "30") (name "Net-(U$10-PadSDO)") (class "Default")
      (node (ref "U$10") (pin "SDO") (pinfunction "SDO_SDO") (pintype "bidirectional"))
      (node (ref "U$11") (pin "SDI") (pinfunction "SDI_SDI") (pintype "bidirectional"))
    )
    (net (code "31") (name "Net-(U$11-PadCLKO)") (class "Default")
      (node (ref "U$11") (pin "CLKO") (pinfunction "CLKO_CLKO") (pintype "bidirectional"))
      (node (ref "U$12") (pin "CLKI") (pinfunction "CLKI_CLKI") (pintype "bidirectional"))
    )
    (net (code "32") (name "Net-(U$11-PadSDO)") (class "Default")
      (node (ref "U$11") (pin "SDO") (pinfunction "SDO_SDO") (pintype "bidirectional"))
      (node (ref "U$12") (pin "SDI") (pinfunction "SDI_SDI") (pintype "bidirectional"))
    )
    (net (code "33") (name "Net-(U$12-PadCLKO)") (class "Default")
      (node (ref "U$12") (pin "CLKO") (pinfunction "CLKO_CLKO") (pintype "bidirectional"))
      (node (ref "U$13") (pin "CLKI") (pinfunction "CLKI_CLKI") (pintype "bidirectional"))
    )
    (net (code "34") (name "Net-(U$12-PadSDO)") (class "Default")
      (node (ref "U$12") (pin "SDO") (pinfunction "SDO_SDO") (pintype "bidirectional"))
      (node (ref "U$13") (pin "SDI") (pinfunction "SDI_SDI") (pintype "bidirectional"))
    )
    (net (code "35") (name "Net-(U$13-PadCLKO)") (class "Default")
      (node (ref "U$13") (pin "CLKO") (pinfunction "CLKO_CLKO") (pintype "bidirectional"))
      (node (ref "U$14") (pin "CLKI") (pinfunction "CLKI_CLKI") (pintype "bidirectional"))
    )
    (net (code "36") (name "Net-(U$13-PadSDO)") (class "Default")
      (node (ref "U$13") (pin "SDO") (pinfunction "SDO_SDO") (pintype "bidirectional"))
      (node (ref "U$14") (pin "SDI") (pinfunction "SDI_SDI") (pintype "bidirectional"))
    )
    (net (code "37") (name "Net-(U$14-PadCLKO)") (class "Default")
      (node (ref "U$14") (pin "CLKO") (pinfunction "CLKO_CLKO") (pintype "bidirectional"))
      (node (ref "U$15") (pin "CLKI") (pinfunction "CLKI_CLKI") (pintype "bidirectional"))
    )
    (net (code "38") (name "Net-(U$14-PadSDO)") (class "Default")
      (node (ref "U$14") (pin "SDO") (pinfunction "SDO_SDO") (pintype "bidirectional"))
      (node (ref "U$15") (pin "SDI") (pinfunction "SDI_SDI") (pintype "bidirectional"))
    )
    (net (code "39") (name "Net-(U$15-PadCLKO)") (class "Default")
      (node (ref "U$15") (pin "CLKO") (pinfunction "CLKO_CLKO") (pintype "bidirectional"))
      (node (ref "U$16") (pin "CLKI") (pinfunction "CLKI_CLKI") (pintype "bidirectional"))
    )
    (net (code "40") (name "Net-(U$15-PadSDO)") (class "Default")
      (node (ref "U$15") (pin "SDO") (pinfunction "SDO_SDO") (pintype "bidirectional"))
      (node (ref "U$16") (pin "SDI") (pinfunction "SDI_SDI") (pintype "bidirectional"))
    )
    (net (code "41") (name "Net-(U$16-PadCLKO)") (class "Default")
      (node (ref "U$16") (pin "CLKO") (pinfunction "CLKO_CLKO") (pintype "bidirectional"))
      (node (ref "U$17") (pin "CLKI") (pinfunction "CLKI_CLKI") (pintype "bidirectional"))
    )
    (net (code "42") (name "Net-(U$16-PadSDO)") (class "Default")
      (node (ref "U$16") (pin "SDO") (pinfunction "SDO_SDO") (pintype "bidirectional"))
      (node (ref "U$17") (pin "SDI") (pinfunction "SDI_SDI") (pintype "bidirectional"))
    )
    (net (code "43") (name "Net-(U$17-PadCLKO)") (class "Default")
      (node (ref "U$17") (pin "CLKO") (pinfunction "CLKO_CLKO") (pintype "bidirectional"))
      (node (ref "U$18") (pin "CLKI") (pinfunction "CLKI_CLKI") (pintype "bidirectional"))
    )
    (net (code "44") (name "Net-(U$17-PadSDO)") (class "Default")
      (node (ref "U$17") (pin "SDO") (pinfunction "SDO_SDO") (pintype "bidirectional"))
      (node (ref "U$18") (pin "SDI") (pinfunction "SDI_SDI") (pintype "bidirectional"))
    )
    (net (code "45") (name "Net-(U$18-PadCLKO)") (class "Default")
      (node (ref "U$18") (pin "CLKO") (pinfunction "CLKO_CLKO") (pintype "bidirectional"))
      (node (ref "U$19") (pin "CLKI") (pinfunction "CLKI_CLKI") (pintype "bidirectional"))
    )
    (net (code "46") (name "Net-(U$18-PadSDO)") (class "Default")
      (node (ref "U$18") (pin "SDO") (pinfunction "SDO_SDO") (pintype "bidirectional"))
      (node (ref "U$19") (pin "SDI") (pinfunction "SDI_SDI") (pintype "bidirectional"))
    )
    (net (code "47") (name "Net-(U$19-PadCLKO)") (class "Default")
      (node (ref "U$19") (pin "CLKO") (pinfunction "CLKO_CLKO") (pintype "bidirectional"))
      (node (ref "U$20") (pin "CLKI") (pinfunction "CLKI_CLKI") (pintype "bidirectional"))
    )
    (net (code "48") (name "Net-(U$19-PadSDO)") (class "Default")
      (node (ref "U$19") (pin "SDO") (pinfunction "SDO_SDO") (pintype "bidirectional"))
      (node (ref "U$20") (pin "SDI") (pinfunction "SDI_SDI") (pintype "bidirectional"))
    )
    (net (code "49") (name "Net-(U$20-PadCLKO)") (class "Default")
      (node (ref "U$20") (pin "CLKO") (pinfunction "CLKO_CLKO") (pintype "bidirectional"))
      (node (ref "U$21") (pin "CLKI") (pinfunction "CLKI_CLKI") (pintype "bidirectional"))
    )
    (net (code "50") (name "Net-(U$20-PadSDO)") (class "Default")
      (node (ref "U$20") (pin "SDO") (pinfunction "SDO_SDO") (pintype "bidirectional"))
      (node (ref "U$21") (pin "SDI") (pinfunction "SDI_SDI") (pintype "bidirectional"))
    )
    (net (code "51") (name "Net-(U$21-PadCLKO)") (class "Default")
      (node (ref "U$21") (pin "CLKO") (pinfunction "CLKO_CLKO") (pintype "bidirectional"))
      (node (ref "U$22") (pin "CLKI") (pinfunction "CLKI_CLKI") (pintype "bidirectional"))
    )
    (net (code "52") (name "Net-(U$21-PadSDO)") (class "Default")
      (node (ref "U$21") (pin "SDO") (pinfunction "SDO_SDO") (pintype "bidirectional"))
      (node (ref "U$22") (pin "SDI") (pinfunction "SDI_SDI") (pintype "bidirectional"))
    )
    (net (code "53") (name "Net-(U$22-PadCLKO)") (class "Default")
      (node (ref "U$22") (pin "CLKO") (pinfunction "CLKO_CLKO") (pintype "bidirectional"))
      (node (ref "U$23") (pin "CLKI") (pinfunction "CLKI_CLKI") (pintype "bidirectional"))
    )
    (net (code "54") (name "Net-(U$22-PadSDO)") (class "Default")
      (node (ref "U$22") (pin "SDO") (pinfunction "SDO_SDO") (pintype "bidirectional"))
      (node (ref "U$23") (pin "SDI") (pinfunction "SDI_SDI") (pintype "bidirectional"))
    )
    (net (code "55") (name "Net-(U$23-PadCLKO)") (class "Default")
      (node (ref "U$23") (pin "CLKO") (pinfunction "CLKO_CLKO") (pintype "bidirectional"))
      (node (ref "U$24") (pin "CLKI") (pinfunction "CLKI_CLKI") (pintype "bidirectional"))
    )
    (net (code "56") (name "Net-(U$23-PadSDO)") (class "Default")
      (node (ref "U$23") (pin "SDO") (pinfunction "SDO_SDO") (pintype "bidirectional"))
      (node (ref "U$24") (pin "SDI") (pinfunction "SDI_SDI") (pintype "bidirectional"))
    )
    (net (code "57") (name "Net-(U$24-PadCLKO)") (class "Default")
      (node (ref "U$24") (pin "CLKO") (pinfunction "CLKO_CLKO") (pintype "bidirectional"))
      (node (ref "U$25") (pin "CLKI") (pinfunction "CLKI_CLKI") (pintype "bidirectional"))
    )
    (net (code "58") (name "Net-(U$24-PadSDO)") (class "Default")
      (node (ref "U$24") (pin "SDO") (pinfunction "SDO_SDO") (pintype "bidirectional"))
      (node (ref "U$25") (pin "SDI") (pinfunction "SDI_SDI") (pintype "bidirectional"))
    )
    (net (code "59") (name "Net-(U$25-PadCLKO)") (class "Default")
      (node (ref "U$25") (pin "CLKO") (pinfunction "CLKO_CLKO") (pintype "bidirectional"))
      (node (ref "U$26") (pin "CLKI") (pinfunction "CLKI_CLKI") (pintype "bidirectional"))
    )
    (net (code "60") (name "Net-(U$25-PadSDO)") (class "Default")
      (node (ref "U$25") (pin "SDO") (pinfunction "SDO_SDO") (pintype "bidirectional"))
      (node (ref "U$26") (pin "SDI") (pinfunction "SDI_SDI") (pintype "bidirectional"))
    )
    (net (code "61") (name "Net-(U$26-PadCLKO)") (class "Default")
      (node (ref "U$26") (pin "CLKO") (pinfunction "CLKO_CLKO") (pintype "bidirectional"))
      (node (ref "U$27") (pin "CLKI") (pinfunction "CLKI_CLKI") (pintype "bidirectional"))
    )
    (net (code "62") (name "Net-(U$26-PadSDO)") (class "Default")
      (node (ref "U$26") (pin "SDO") (pinfunction "SDO_SDO") (pintype "bidirectional"))
      (node (ref "U$27") (pin "SDI") (pinfunction "SDI_SDI") (pintype "bidirectional"))
    )
    (net (code "63") (name "Net-(U$27-PadCLKO)") (class "Default")
      (node (ref "U$27") (pin "CLKO") (pinfunction "CLKO_CLKO") (pintype "bidirectional"))
      (node (ref "U$28") (pin "CLKI") (pinfunction "CLKI_CLKI") (pintype "bidirectional"))
    )
    (net (code "64") (name "Net-(U$27-PadSDO)") (class "Default")
      (node (ref "U$27") (pin "SDO") (pinfunction "SDO_SDO") (pintype "bidirectional"))
      (node (ref "U$28") (pin "SDI") (pinfunction "SDI_SDI") (pintype "bidirectional"))
    )
    (net (code "65") (name "Net-(U$28-PadCLKO)") (class "Default")
      (node (ref "U$28") (pin "CLKO") (pinfunction "CLKO_CLKO") (pintype "bidirectional"))
      (node (ref "U$29") (pin "CLKI") (pinfunction "CLKI_CLKI") (pintype "bidirectional"))
    )
    (net (code "66") (name "Net-(U$28-PadSDO)") (class "Default")
      (node (ref "U$28") (pin "SDO") (pinfunction "SDO_SDO") (pintype "bidirectional"))
      (node (ref "U$29") (pin "SDI") (pinfunction "SDI_SDI") (pintype "bidirectional"))
    )
    (net (code "67") (name "Net-(U$29-PadCLKO)") (class "Default")
      (node (ref "U$29") (pin "CLKO") (pinfunction "CLKO_CLKO") (pintype "bidirectional"))
      (node (ref "U$30") (pin "CLKI") (pinfunction "CLKI_CLKI") (pintype "bidirectional"))
    )
    (net (code "68") (name "Net-(U$29-PadSDO)") (class "Default")
      (node (ref "U$29") (pin "SDO") (pinfunction "SDO_SDO") (pintype "bidirectional"))
      (node (ref "U$30") (pin "SDI") (pinfunction "SDI_SDI") (pintype "bidirectional"))
    )
    (net (code "69") (name "Net-(U$30-PadCLKO)") (class "Default")
      (node (ref "U$30") (pin "CLKO") (pinfunction "CLKO_CLKO") (pintype "bidirectional"))
      (node (ref "U$31") (pin "CLKI") (pinfunction "CLKI_CLKI") (pintype "bidirectional"))
    )
    (net (code "70") (name "Net-(U$30-PadSDO)") (class "Default")
      (node (ref "U$30") (pin "SDO") (pinfunction "SDO_SDO") (pintype "bidirectional"))
      (node (ref "U$31") (pin "SDI") (pinfunction "SDI_SDI") (pintype "bidirectional"))
    )
    (net (code "71") (name "Net-(U$31-PadCLKO)") (class "Default")
      (node (ref "U$31") (pin "CLKO") (pinfunction "CLKO_CLKO") (pintype "bidirectional"))
      (node (ref "U$32") (pin "CLKI") (pinfunction "CLKI_CLKI") (pintype "bidirectional"))
    )
    (net (code "72") (name "Net-(U$31-PadSDO)") (class "Default")
      (node (ref "U$31") (pin "SDO") (pinfunction "SDO_SDO") (pintype "bidirectional"))
      (node (ref "U$32") (pin "SDI") (pinfunction "SDI_SDI") (pintype "bidirectional"))
    )
    (net (code "73") (name "Net-(U$32-PadCLKO)") (class "Default")
      (node (ref "U$32") (pin "CLKO") (pinfunction "CLKO_CLKO") (pintype "bidirectional"))
      (node (ref "U$33") (pin "CLKI") (pinfunction "CLKI_CLKI") (pintype "bidirectional"))
    )
    (net (code "74") (name "Net-(U$32-PadSDO)") (class "Default")
      (node (ref "U$32") (pin "SDO") (pinfunction "SDO_SDO") (pintype "bidirectional"))
      (node (ref "U$33") (pin "SDI") (pinfunction "SDI_SDI") (pintype "bidirectional"))
    )
    (net (code "75") (name "Net-(U$33-PadCLKO)") (class "Default")
      (node (ref "U$33") (pin "CLKO") (pinfunction "CLKO_CLKO") (pintype "bidirectional"))
      (node (ref "U$34") (pin "CLKI") (pinfunction "CLKI_CLKI") (pintype "bidirectional"))
    )
    (net (code "76") (name "Net-(U$33-PadSDO)") (class "Default")
      (node (ref "U$33") (pin "SDO") (pinfunction "SDO_SDO") (pintype "bidirectional"))
      (node (ref "U$34") (pin "SDI") (pinfunction "SDI_SDI") (pintype "bidirectional"))
    )
    (net (code "77") (name "Net-(U$34-PadCLKO)") (class "Default")
      (node (ref "U$34") (pin "CLKO") (pinfunction "CLKO_CLKO") (pintype "bidirectional"))
      (node (ref "U$35") (pin "CLKI") (pinfunction "CLKI_CLKI") (pintype "bidirectional"))
    )
    (net (code "78") (name "Net-(U$34-PadSDO)") (class "Default")
      (node (ref "U$34") (pin "SDO") (pinfunction "SDO_SDO") (pintype "bidirectional"))
      (node (ref "U$35") (pin "SDI") (pinfunction "SDI_SDI") (pintype "bidirectional"))
    )
    (net (code "79") (name "Net-(U$35-PadCLKO)") (class "Default")
      (node (ref "U$35") (pin "CLKO") (pinfunction "CLKO_CLKO") (pintype "bidirectional"))
      (node (ref "U$36") (pin "CLKI") (pinfunction "CLKI_CLKI") (pintype "bidirectional"))
    )
    (net (code "80") (name "Net-(U$35-PadSDO)") (class "Default")
      (node (ref "U$35") (pin "SDO") (pinfunction "SDO_SDO") (pintype "bidirectional"))
      (node (ref "U$36") (pin "SDI") (pinfunction "SDI_SDI") (pintype "bidirectional"))
    )
    (net (code "81") (name "Net-(U$36-PadCLKO)") (class "Default")
      (node (ref "U$36") (pin "CLKO") (pinfunction "CLKO_CLKO") (pintype "bidirectional"))
      (node (ref "U$37") (pin "CLKI") (pinfunction "CLKI_CLKI") (pintype "bidirectional"))
    )
    (net (code "82") (name "Net-(U$36-PadSDO)") (class "Default")
      (node (ref "U$36") (pin "SDO") (pinfunction "SDO_SDO") (pintype "bidirectional"))
      (node (ref "U$37") (pin "SDI") (pinfunction "SDI_SDI") (pintype "bidirectional"))
    )
    (net (code "83") (name "Net-(U$37-PadCLKO)") (class "Default")
      (node (ref "U$37") (pin "CLKO") (pinfunction "CLKO_CLKO") (pintype "bidirectional"))
      (node (ref "U$38") (pin "CLKI") (pinfunction "CLKI_CLKI") (pintype "bidirectional"))
    )
    (net (code "84") (name "Net-(U$37-PadSDO)") (class "Default")
      (node (ref "U$37") (pin "SDO") (pinfunction "SDO_SDO") (pintype "bidirectional"))
      (node (ref "U$38") (pin "SDI") (pinfunction "SDI_SDI") (pintype "bidirectional"))
    )
    (net (code "85") (name "Net-(U$38-PadCLKO)") (class "Default")
      (node (ref "U$38") (pin "CLKO") (pinfunction "CLKO_CLKO") (pintype "bidirectional"))
      (node (ref "U$39") (pin "CLKI") (pinfunction "CLKI_CLKI") (pintype "bidirectional"))
    )
    (net (code "86") (name "Net-(U$38-PadSDO)") (class "Default")
      (node (ref "U$38") (pin "SDO") (pinfunction "SDO_SDO") (pintype "bidirectional"))
      (node (ref "U$39") (pin "SDI") (pinfunction "SDI_SDI") (pintype "bidirectional"))
    )
    (net (code "87") (name "Net-(U$39-PadCLKO)") (class "Default")
      (node (ref "U$39") (pin "CLKO") (pinfunction "CLKO_CLKO") (pintype "bidirectional"))
      (node (ref "U$40") (pin "CLKI") (pinfunction "CLKI_CLKI") (pintype "bidirectional"))
    )
    (net (code "88") (name "Net-(U$39-PadSDO)") (class "Default")
      (node (ref "U$39") (pin "SDO") (pinfunction "SDO_SDO") (pintype "bidirectional"))
      (node (ref "U$40") (pin "SDI") (pinfunction "SDI_SDI") (pintype "bidirectional"))
    )
    (net (code "89") (name "Net-(U$40-PadCLKO)") (class "Default")
      (node (ref "U$40") (pin "CLKO") (pinfunction "CLKO_CLKO") (pintype "bidirectional"))
      (node (ref "U$41") (pin "CLKI") (pinfunction "CLKI_CLKI") (pintype "bidirectional"))
    )
    (net (code "90") (name "Net-(U$40-PadSDO)") (class "Default")
      (node (ref "U$40") (pin "SDO") (pinfunction "SDO_SDO") (pintype "bidirectional"))
      (node (ref "U$41") (pin "SDI") (pinfunction "SDI_SDI") (pintype "bidirectional"))
    )
    (net (code "91") (name "Net-(U$41-PadCLKO)") (class "Default")
      (node (ref "U$41") (pin "CLKO") (pinfunction "CLKO_CLKO") (pintype "bidirectional"))
      (node (ref "U$42") (pin "CLKI") (pinfunction "CLKI_CLKI") (pintype "bidirectional"))
    )
    (net (code "92") (name "Net-(U$41-PadSDO)") (class "Default")
      (node (ref "U$41") (pin "SDO") (pinfunction "SDO_SDO") (pintype "bidirectional"))
      (node (ref "U$42") (pin "SDI") (pinfunction "SDI_SDI") (pintype "bidirectional"))
    )
    (net (code "93") (name "Net-(U$42-PadCLKO)") (class "Default")
      (node (ref "U$42") (pin "CLKO") (pinfunction "CLKO_CLKO") (pintype "bidirectional"))
      (node (ref "U$43") (pin "CLKI") (pinfunction "CLKI_CLKI") (pintype "bidirectional"))
    )
    (net (code "94") (name "Net-(U$42-PadSDO)") (class "Default")
      (node (ref "U$42") (pin "SDO") (pinfunction "SDO_SDO") (pintype "bidirectional"))
      (node (ref "U$43") (pin "SDI") (pinfunction "SDI_SDI") (pintype "bidirectional"))
    )
    (net (code "95") (name "Net-(U$43-PadCLKO)") (class "Default")
      (node (ref "U$43") (pin "CLKO") (pinfunction "CLKO_CLKO") (pintype "bidirectional"))
      (node (ref "U$44") (pin "CLKI") (pinfunction "CLKI_CLKI") (pintype "bidirectional"))
    )
    (net (code "96") (name "Net-(U$43-PadSDO)") (class "Default")
      (node (ref "U$43") (pin "SDO") (pinfunction "SDO_SDO") (pintype "bidirectional"))
      (node (ref "U$44") (pin "SDI") (pinfunction "SDI_SDI") (pintype "bidirectional"))
    )
    (net (code "97") (name "Net-(U$44-PadCLKO)") (class "Default")
      (node (ref "U$44") (pin "CLKO") (pinfunction "CLKO_CLKO") (pintype "bidirectional"))
      (node (ref "U$45") (pin "CLKI") (pinfunction "CLKI_CLKI") (pintype "bidirectional"))
    )
    (net (code "98") (name "Net-(U$44-PadSDO)") (class "Default")
      (node (ref "U$44") (pin "SDO") (pinfunction "SDO_SDO") (pintype "bidirectional"))
      (node (ref "U$45") (pin "SDI") (pinfunction "SDI_SDI") (pintype "bidirectional"))
    )
    (net (code "99") (name "Net-(U$45-PadCLKO)") (class "Default")
      (node (ref "U$45") (pin "CLKO") (pinfunction "CLKO_CLKO") (pintype "bidirectional"))
      (node (ref "U$46") (pin "CLKI") (pinfunction "CLKI_CLKI") (pintype "bidirectional"))
    )
    (net (code "100") (name "Net-(U$45-PadSDO)") (class "Default")
      (node (ref "U$45") (pin "SDO") (pinfunction "SDO_SDO") (pintype "bidirectional"))
      (node (ref "U$46") (pin "SDI") (pinfunction "SDI_SDI") (pintype "bidirectional"))
    )
    (net (code "101") (name "Net-(U$46-PadCLKO)") (class "Default")
      (node (ref "U$46") (pin "CLKO") (pinfunction "CLKO_CLKO") (pintype "bidirectional"))
      (node (ref "U$47") (pin "CLKI") (pinfunction "CLKI_CLKI") (pintype "bidirectional"))
    )
    (net (code "102") (name "Net-(U$46-PadSDO)") (class "Default")
      (node (ref "U$46") (pin "SDO") (pinfunction "SDO_SDO") (pintype "bidirectional"))
      (node (ref "U$47") (pin "SDI") (pinfunction "SDI_SDI") (pintype "bidirectional"))
    )
    (net (code "103") (name "Net-(U$47-PadCLKO)") (class "Default")
      (node (ref "U$47") (pin "CLKO") (pinfunction "CLKO_CLKO") (pintype "bidirectional"))
      (node (ref "U$48") (pin "CLKI") (pinfunction "CLKI_CLKI") (pintype "bidirectional"))
    )
    (net (code "104") (name "Net-(U$47-PadSDO)") (class "Default")
      (node (ref "U$47") (pin "SDO") (pinfunction "SDO_SDO") (pintype "bidirectional"))
      (node (ref "U$48") (pin "SDI") (pinfunction "SDI_SDI") (pintype "bidirectional"))
    )
    (net (code "105") (name "Net-(U$48-PadCLKO)") (class "Default")
      (node (ref "U$48") (pin "CLKO") (pinfunction "CLKO_CLKO") (pintype "bidirectional"))
      (node (ref "U$49") (pin "CLKI") (pinfunction "CLKI_CLKI") (pintype "bidirectional"))
    )
    (net (code "106") (name "Net-(U$48-PadSDO)") (class "Default")
      (node (ref "U$48") (pin "SDO") (pinfunction "SDO_SDO") (pintype "bidirectional"))
      (node (ref "U$49") (pin "SDI") (pinfunction "SDI_SDI") (pintype "bidirectional"))
    )
    (net (code "107") (name "Net-(U$49-PadCLKO)") (class "Default")
      (node (ref "U$49") (pin "CLKO") (pinfunction "CLKO_CLKO") (pintype "bidirectional"))
      (node (ref "U$50") (pin "CLKI") (pinfunction "CLKI_CLKI") (pintype "bidirectional"))
    )
    (net (code "108") (name "Net-(U$49-PadSDO)") (class "Default")
      (node (ref "U$49") (pin "SDO") (pinfunction "SDO_SDO") (pintype "bidirectional"))
      (node (ref "U$50") (pin "SDI") (pinfunction "SDI_SDI") (pintype "bidirectional"))
    )
    (net (code "109") (name "Net-(U$50-PadCLKO)") (class "Default")
      (node (ref "U$50") (pin "CLKO") (pinfunction "CLKO_CLKO") (pintype "bidirectional"))
      (node (ref "U$51") (pin "CLKI") (pinfunction "CLKI_CLKI") (pintype "bidirectional"))
    )
    (net (code "110") (name "Net-(U$50-PadSDO)") (class "Default")
      (node (ref "U$50") (pin "SDO") (pinfunction "SDO_SDO") (pintype "bidirectional"))
      (node (ref "U$51") (pin "SDI") (pinfunction "SDI_SDI") (pintype "bidirectional"))
    )
    (net (code "111") (name "Net-(U$51-PadCLKO)") (class "Default")
      (node (ref "U$51") (pin "CLKO") (pinfunction "CLKO_CLKO") (pintype "bidirectional"))
      (node (ref "U$52") (pin "CLKI") (pinfunction "CLKI_CLKI") (pintype "bidirectional"))
    )
    (net (code "112") (name "Net-(U$51-PadSDO)") (class "Default")
      (node (ref "U$51") (pin "SDO") (pinfunction "SDO_SDO") (pintype "bidirectional"))
      (node (ref "U$52") (pin "SDI") (pinfunction "SDI_SDI") (pintype "bidirectional"))
    )
    (net (code "113") (name "Net-(U$52-PadCLKO)") (class "Default")
      (node (ref "U$52") (pin "CLKO") (pinfunction "CLKO_CLKO") (pintype "bidirectional"))
      (node (ref "U$53") (pin "CLKI") (pinfunction "CLKI_CLKI") (pintype "bidirectional"))
    )
    (net (code "114") (name "Net-(U$52-PadSDO)") (class "Default")
      (node (ref "U$52") (pin "SDO") (pinfunction "SDO_SDO") (pintype "bidirectional"))
      (node (ref "U$53") (pin "SDI") (pinfunction "SDI_SDI") (pintype "bidirectional"))
    )
    (net (code "115") (name "Net-(U$53-PadCLKO)") (class "Default")
      (node (ref "U$53") (pin "CLKO") (pinfunction "CLKO_CLKO") (pintype "bidirectional"))
      (node (ref "U$54") (pin "CLKI") (pinfunction "CLKI_CLKI") (pintype "bidirectional"))
    )
    (net (code "116") (name "Net-(U$53-PadSDO)") (class "Default")
      (node (ref "U$53") (pin "SDO") (pinfunction "SDO_SDO") (pintype "bidirectional"))
      (node (ref "U$54") (pin "SDI") (pinfunction "SDI_SDI") (pintype "bidirectional"))
    )
    (net (code "117") (name "Net-(U$54-PadCLKO)") (class "Default")
      (node (ref "U$54") (pin "CLKO") (pinfunction "CLKO_CLKO") (pintype "bidirectional"))
      (node (ref "U$55") (pin "CLKI") (pinfunction "CLKI_CLKI") (pintype "bidirectional"))
    )
    (net (code "118") (name "Net-(U$54-PadSDO)") (class "Default")
      (node (ref "U$54") (pin "SDO") (pinfunction "SDO_SDO") (pintype "bidirectional"))
      (node (ref "U$55") (pin "SDI") (pinfunction "SDI_SDI") (pintype "bidirectional"))
    )
    (net (code "119") (name "Net-(U$55-PadCLKO)") (class "Default")
      (node (ref "U$55") (pin "CLKO") (pinfunction "CLKO_CLKO") (pintype "bidirectional"))
      (node (ref "U$56") (pin "CLKI") (pinfunction "CLKI_CLKI") (pintype "bidirectional"))
    )
    (net (code "120") (name "Net-(U$55-PadSDO)") (class "Default")
      (node (ref "U$55") (pin "SDO") (pinfunction "SDO_SDO") (pintype "bidirectional"))
      (node (ref "U$56") (pin "SDI") (pinfunction "SDI_SDI") (pintype "bidirectional"))
    )
    (net (code "121") (name "Net-(U$56-PadCLKO)") (class "Default")
      (node (ref "U$56") (pin "CLKO") (pinfunction "CLKO_CLKO") (pintype "bidirectional"))
      (node (ref "U$57") (pin "CLKI") (pinfunction "CLKI_CLKI") (pintype "bidirectional"))
    )
    (net (code "122") (name "Net-(U$56-PadSDO)") (class "Default")
      (node (ref "U$56") (pin "SDO") (pinfunction "SDO_SDO") (pintype "bidirectional"))
      (node (ref "U$57") (pin "SDI") (pinfunction "SDI_SDI") (pintype "bidirectional"))
    )
    (net (code "123") (name "Net-(U$57-PadCLKO)") (class "Default")
      (node (ref "U$57") (pin "CLKO") (pinfunction "CLKO_CLKO") (pintype "bidirectional"))
      (node (ref "U$58") (pin "CLKI") (pinfunction "CLKI_CLKI") (pintype "bidirectional"))
    )
    (net (code "124") (name "Net-(U$57-PadSDO)") (class "Default")
      (node (ref "U$57") (pin "SDO") (pinfunction "SDO_SDO") (pintype "bidirectional"))
      (node (ref "U$58") (pin "SDI") (pinfunction "SDI_SDI") (pintype "bidirectional"))
    )
    (net (code "125") (name "Net-(U$58-PadCLKO)") (class "Default")
      (node (ref "U$58") (pin "CLKO") (pinfunction "CLKO_CLKO") (pintype "bidirectional"))
      (node (ref "U$59") (pin "CLKI") (pinfunction "CLKI_CLKI") (pintype "bidirectional"))
    )
    (net (code "126") (name "Net-(U$58-PadSDO)") (class "Default")
      (node (ref "U$58") (pin "SDO") (pinfunction "SDO_SDO") (pintype "bidirectional"))
      (node (ref "U$59") (pin "SDI") (pinfunction "SDI_SDI") (pintype "bidirectional"))
    )
    (net (code "127") (name "Net-(U$59-PadCLKO)") (class "Default")
      (node (ref "U$59") (pin "CLKO") (pinfunction "CLKO_CLKO") (pintype "bidirectional"))
      (node (ref "U$60") (pin "CLKI") (pinfunction "CLKI_CLKI") (pintype "bidirectional"))
    )
    (net (code "128") (name "Net-(U$59-PadSDO)") (class "Default")
      (node (ref "U$59") (pin "SDO") (pinfunction "SDO_SDO") (pintype "bidirectional"))
      (node (ref "U$60") (pin "SDI") (pinfunction "SDI_SDI") (pintype "bidirectional"))
    )
    (net (code "129") (name "Net-(U$60-PadCLKO)") (class "Default")
      (node (ref "U$60") (pin "CLKO") (pinfunction "CLKO_CLKO") (pintype "bidirectional"))
      (node (ref "U$61") (pin "CLKI") (pinfunction "CLKI_CLKI") (pintype "bidirectional"))
    )
    (net (code "130") (name "Net-(U$60-PadSDO)") (class "Default")
      (node (ref "U$60") (pin "SDO") (pinfunction "SDO_SDO") (pintype "bidirectional"))
      (node (ref "U$61") (pin "SDI") (pinfunction "SDI_SDI") (pintype "bidirectional"))
    )
    (net (code "131") (name "Net-(U$61-PadCLKO)") (class "Default")
      (node (ref "U$61") (pin "CLKO") (pinfunction "CLKO_CLKO") (pintype "bidirectional"))
      (node (ref "U$62") (pin "CLKI") (pinfunction "CLKI_CLKI") (pintype "bidirectional"))
    )
    (net (code "132") (name "Net-(U$61-PadSDO)") (class "Default")
      (node (ref "U$61") (pin "SDO") (pinfunction "SDO_SDO") (pintype "bidirectional"))
      (node (ref "U$62") (pin "SDI") (pinfunction "SDI_SDI") (pintype "bidirectional"))
    )
    (net (code "133") (name "Net-(U$62-PadCLKO)") (class "Default")
      (node (ref "U$62") (pin "CLKO") (pinfunction "CLKO_CLKO") (pintype "bidirectional"))
      (node (ref "U$63") (pin "CLKI") (pinfunction "CLKI_CLKI") (pintype "bidirectional"))
    )
    (net (code "134") (name "Net-(U$62-PadSDO)") (class "Default")
      (node (ref "U$62") (pin "SDO") (pinfunction "SDO_SDO") (pintype "bidirectional"))
      (node (ref "U$63") (pin "SDI") (pinfunction "SDI_SDI") (pintype "bidirectional"))
    )
    (net (code "135") (name "Net-(U$63-PadCLKO)") (class "Default")
      (node (ref "U$63") (pin "CLKO") (pinfunction "CLKO_CLKO") (pintype "bidirectional"))
      (node (ref "U$64") (pin "CLKI") (pinfunction "CLKI_CLKI") (pintype "bidirectional"))
    )
    (net (code "136") (name "Net-(U$63-PadSDO)") (class "Default")
      (node (ref "U$63") (pin "SDO") (pinfunction "SDO_SDO") (pintype "bidirectional"))
      (node (ref "U$64") (pin "SDI") (pinfunction "SDI_SDI") (pintype "bidirectional"))
    )
    (net (code "137") (name "Net-(U$64-PadCLKO)") (class "Default")
      (node (ref "U$64") (pin "CLKO") (pinfunction "CLKO_CLKO") (pintype "bidirectional"))
      (node (ref "U$65") (pin "CLKI") (pinfunction "CLKI_CLKI") (pintype "bidirectional"))
    )
    (net (code "138") (name "Net-(U$64-PadSDO)") (class "Default")
      (node (ref "U$64") (pin "SDO") (pinfunction "SDO_SDO") (pintype "bidirectional"))
      (node (ref "U$65") (pin "SDI") (pinfunction "SDI_SDI") (pintype "bidirectional"))
    )
    (net (code "139") (name "Net-(U$65-PadCLKO)") (class "Default")
      (node (ref "U$65") (pin "CLKO") (pinfunction "CLKO_CLKO") (pintype "bidirectional"))
      (node (ref "U$66") (pin "CLKI") (pinfunction "CLKI_CLKI") (pintype "bidirectional"))
    )
    (net (code "140") (name "Net-(U$65-PadSDO)") (class "Default")
      (node (ref "U$65") (pin "SDO") (pinfunction "SDO_SDO") (pintype "bidirectional"))
      (node (ref "U$66") (pin "SDI") (pinfunction "SDI_SDI") (pintype "bidirectional"))
    )
    (net (code "141") (name "Net-(U$66-PadCLKO)") (class "Default")
      (node (ref "U$66") (pin "CLKO") (pinfunction "CLKO_CLKO") (pintype "bidirectional"))
      (node (ref "U$67") (pin "CLKI") (pinfunction "CLKI_CLKI") (pintype "bidirectional"))
    )
    (net (code "142") (name "Net-(U$66-PadSDO)") (class "Default")
      (node (ref "U$66") (pin "SDO") (pinfunction "SDO_SDO") (pintype "bidirectional"))
      (node (ref "U$67") (pin "SDI") (pinfunction "SDI_SDI") (pintype "bidirectional"))
    )
    (net (code "143") (name "Net-(U$67-PadCLKO)") (class "Default")
      (node (ref "U$67") (pin "CLKO") (pinfunction "CLKO_CLKO") (pintype "bidirectional"))
      (node (ref "U$68") (pin "CLKI") (pinfunction "CLKI_CLKI") (pintype "bidirectional"))
    )
    (net (code "144") (name "Net-(U$67-PadSDO)") (class "Default")
      (node (ref "U$67") (pin "SDO") (pinfunction "SDO_SDO") (pintype "bidirectional"))
      (node (ref "U$68") (pin "SDI") (pinfunction "SDI_SDI") (pintype "bidirectional"))
    )
    (net (code "145") (name "Net-(U$68-PadCLKO)") (class "Default")
      (node (ref "U$68") (pin "CLKO") (pinfunction "CLKO_CLKO") (pintype "bidirectional"))
      (node (ref "U$69") (pin "CLKI") (pinfunction "CLKI_CLKI") (pintype "bidirectional"))
    )
    (net (code "146") (name "Net-(U$68-PadSDO)") (class "Default")
      (node (ref "U$68") (pin "SDO") (pinfunction "SDO_SDO") (pintype "bidirectional"))
      (node (ref "U$69") (pin "SDI") (pinfunction "SDI_SDI") (pintype "bidirectional"))
    )
    (net (code "147") (name "Net-(U$69-PadCLKO)") (class "Default")
      (node (ref "U$69") (pin "CLKO") (pinfunction "CLKO_CLKO") (pintype "bidirectional"))
      (node (ref "U$70") (pin "CLKI") (pinfunction "CLKI_CLKI") (pintype "bidirectional"))
    )
    (net (code "148") (name "Net-(U$69-PadSDO)") (class "Default")
      (node (ref "U$69") (pin "SDO") (pinfunction "SDO_SDO") (pintype "bidirectional"))
      (node (ref "U$70") (pin "SDI") (pinfunction "SDI_SDI") (pintype "bidirectional"))
    )
    (net (code "149") (name "Net-(U$70-PadCLKO)") (class "Default")
      (node (ref "U$70") (pin "CLKO") (pinfunction "CLKO_CLKO") (pintype "bidirectional"))
      (node (ref "U$71") (pin "CLKI") (pinfunction "CLKI_CLKI") (pintype "bidirectional"))
    )
    (net (code "150") (name "Net-(U$70-PadSDO)") (class "Default")
      (node (ref "U$70") (pin "SDO") (pinfunction "SDO_SDO") (pintype "bidirectional"))
      (node (ref "U$71") (pin "SDI") (pinfunction "SDI_SDI") (pintype "bidirectional"))
    )
    (net (code "151") (name "Net-(U$71-PadCLKO)") (class "Default")
      (node (ref "U$71") (pin "CLKO") (pinfunction "CLKO_CLKO") (pintype "bidirectional"))
      (node (ref "U$72") (pin "CLKI") (pinfunction "CLKI_CLKI") (pintype "bidirectional"))
    )
    (net (code "152") (name "Net-(U$71-PadSDO)") (class "Default")
      (node (ref "U$71") (pin "SDO") (pinfunction "SDO_SDO") (pintype "bidirectional"))
      (node (ref "U$72") (pin "SDI") (pinfunction "SDI_SDI") (pintype "bidirectional"))
    )
    (net (code "153") (name "Net-(U$72-PadCLKO)") (class "Default")
      (node (ref "U$72") (pin "CLKO") (pinfunction "CLKO_CLKO") (pintype "bidirectional"))
      (node (ref "U$73") (pin "CLKI") (pinfunction "CLKI_CLKI") (pintype "bidirectional"))
    )
    (net (code "154") (name "Net-(U$72-PadSDO)") (class "Default")
      (node (ref "U$72") (pin "SDO") (pinfunction "SDO_SDO") (pintype "bidirectional"))
      (node (ref "U$73") (pin "SDI") (pinfunction "SDI_SDI") (pintype "bidirectional"))
    )
    (net (code "155") (name "Net-(U1-ECOL{slash}RPD10{slash}SCL1{slash}SCK4{slash}RD10)") (class "Default")
      (node (ref "R4") (pin "1") (pinfunction "1_1") (pintype "passive"))
      (node (ref "U1") (pin "44") (pinfunction "ECOL/RPD10/SCL1/SCK4/RD10_44") (pintype "bidirectional"))
    )
    (net (code "156") (name "Net-(U1-EMDIO{slash}AEMDIO{slash}RPD1{slash}SCK1{slash}RD1)") (class "Default")
      (node (ref "R5") (pin "1") (pinfunction "1_1") (pintype "passive"))
      (node (ref "U1") (pin "49") (pinfunction "EMDIO/AEMDIO/RPD1/SCK1/RD1_49") (pintype "bidirectional"))
    )
    (net (code "157") (name "Net-(U1-ETXERR{slash}AETXEN{slash}RPD2{slash}SDA3{slash}RD2)") (class "Default")
      (node (ref "R2") (pin "2") (pinfunction "2_2") (pintype "passive"))
      (node (ref "U1") (pin "50") (pinfunction "ETXERR/AETXEN/RPD2/SDA3/RD2_50") (pintype "bidirectional"))
    )
    (net (code "158") (name "Net-(U1-MCLR)") (class "Default")
      (node (ref "JP2") (pin "5") (pinfunction "5_5") (pintype "passive"))
      (node (ref "R1") (pin "2") (pinfunction "2_2") (pintype "passive"))
      (node (ref "U1") (pin "9") (pinfunction "MCLR_9") (pintype "input"))
    )
    (net (code "159") (name "Net-(U1-PGEC1{slash}VREF-{slash}CVREF-{slash}AN1{slash}RPB1{slash}RB1)") (class "Default")
      (node (ref "JP2") (pin "1") (pinfunction "1_1") (pintype "passive"))
      (node (ref "U1") (pin "15") (pinfunction "PGEC1/VREF-/CVREF-/AN1/RPB1/RB1_15") (pintype "bidirectional"))
    )
    (net (code "160") (name "Net-(U1-PGED1{slash}VREF+{slash}CVREF+{slash}AN0{slash}RPB0{slash}PMA6{slash}RB0)") (class "Default")
      (node (ref "JP2") (pin "2") (pinfunction "2_2") (pintype "passive"))
      (node (ref "U1") (pin "16") (pinfunction "PGED1/VREF+/CVREF+/AN0/RPB0/PMA6/RB0_16") (pintype "bidirectional"))
    )
    (net (code "161") (name "unconnected-(U$73-PadCLKO)") (class "Default")
      (node (ref "U$73") (pin "CLKO") (pinfunction "CLKO_CLKO") (pintype "bidirectional"))
    )
    (net (code "162") (name "unconnected-(U$73-PadSDO)") (class "Default")
      (node (ref "U$73") (pin "SDO") (pinfunction "SDO_SDO") (pintype "bidirectional"))
    )
    (net (code "163") (name "unconnected-(U1-AERXCLK{slash}AEREFCLK{slash}ECRS{slash}RPD11{slash}PMCS1{slash}PMA14{slash}RD11-Pad45)") (class "Default")
      (node (ref "U1") (pin "45") (pinfunction "AERXCLK/AEREFCLK/ECRS/RPD11/PMCS1/PMA14/RD11_45") (pintype "bidirectional"))
    )
    (net (code "164") (name "unconnected-(U1-AERXD0{slash}ETXD2{slash}RPD9{slash}SDA1{slash}PMCS2{slash}PMA15{slash}RD9-Pad43)") (class "Default")
      (node (ref "U1") (pin "43") (pinfunction "AERXD0/ETXD2/RPD9/SDA1/PMCS2/PMA15/RD9_43") (pintype "bidirectional"))
    )
    (net (code "165") (name "unconnected-(U1-AERXD1{slash}ETXD3{slash}RPD0{slash}RTCC{slash}INT0{slash}RD0-Pad46)") (class "Default")
      (node (ref "U1") (pin "46") (pinfunction "AERXD1/ETXD3/RPD0/RTCC/INT0/RD0_46") (pintype "bidirectional"))
    )
    (net (code "166") (name "unconnected-(U1-AERXERR{slash}ETXCLK{slash}RPD3{slash}SCL3{slash}RD3-Pad51)") (class "Default")
      (node (ref "U1") (pin "51") (pinfunction "AERXERR/ETXCLK/RPD3/SCL3/RD3_51") (pintype "bidirectional"))
    )
    (net (code "167") (name "unconnected-(U1-AN2{slash}C2INB{slash}RPB2{slash}RB2-Pad14)") (class "Default")
      (node (ref "U1") (pin "14") (pinfunction "AN2/C2INB/RPB2/RB2_14") (pintype "bidirectional"))
    )
    (net (code "168") (name "unconnected-(U1-AN3{slash}C2INA{slash}RPB3{slash}RB3-Pad13)") (class "Default")
      (node (ref "U1") (pin "13") (pinfunction "AN3/C2INA/RPB3/RB3_13") (pintype "bidirectional"))
    )
    (net (code "169") (name "unconnected-(U1-AN4{slash}C1INB{slash}RB4-Pad12)") (class "Default")
      (node (ref "U1") (pin "12") (pinfunction "AN4/C1INB/RB4_12") (pintype "bidirectional"))
    )
    (net (code "170") (name "unconnected-(U1-AN9{slash}RPB14{slash}SCK3{slash}PMA1{slash}RB14-Pad29)") (class "Default")
      (node (ref "U1") (pin "29") (pinfunction "AN9/RPB14/SCK3/PMA1/RB14_29") (pintype "bidirectional"))
    )
    (net (code "171") (name "unconnected-(U1-AN10{slash}EMDC{slash}AEMDC{slash}RPB15{slash}OCFB{slash}PMA0{slash}RB15-Pad30)") (class "Default")
      (node (ref "U1") (pin "30") (pinfunction "AN10/EMDC/AEMDC/RPB15/OCFB/PMA0/RB15_30") (pintype "bidirectional"))
    )
    (net (code "172") (name "unconnected-(U1-AN11{slash}C2INC{slash}RPG9{slash}PMA2{slash}RG9-Pad10)") (class "Default")
      (node (ref "U1") (pin "10") (pinfunction "AN11/C2INC/RPG9/PMA2/RG9_10") (pintype "bidirectional"))
    )
    (net (code "173") (name "unconnected-(U1-AN12{slash}C2IND{slash}RPG8{slash}SCL4{slash}PMA3{slash}RG8-Pad6)") (class "Default")
      (node (ref "U1") (pin "6") (pinfunction "AN12/C2IND/RPG8/SCL4/PMA3/RG8_6") (pintype "bidirectional"))
    )
    (net (code "174") (name "unconnected-(U1-AN13{slash}C1INC{slash}RPG7{slash}SDA4{slash}PMA4{slash}RG7-Pad5)") (class "Default")
      (node (ref "U1") (pin "5") (pinfunction "AN13/C1INC/RPG7/SDA4/PMA4/RG7_5") (pintype "bidirectional"))
    )
    (net (code "175") (name "unconnected-(U1-AN14{slash}C1IND{slash}RPG6{slash}SCK2{slash}PMA5{slash}RG6-Pad4)") (class "Default")
      (node (ref "U1") (pin "4") (pinfunction "AN14/C1IND/RPG6/SCK2/PMA5/RG6_4") (pintype "bidirectional"))
    )
    (net (code "176") (name "unconnected-(U1-AN15{slash}ETXD1{slash}PMD7{slash}RE7-Pad3)") (class "Default")
      (node (ref "U1") (pin "3") (pinfunction "AN15/ETXD1/PMD7/RE7_3") (pintype "bidirectional"))
    )
    (net (code "177") (name "unconnected-(U1-AN16{slash}ETXD0{slash}PMD6{slash}RE6-Pad2)") (class "Default")
      (node (ref "U1") (pin "2") (pinfunction "AN16/ETXD0/PMD6/RE6_2") (pintype "bidirectional"))
    )
    (net (code "178") (name "unconnected-(U1-AN17{slash}ETXEN{slash}RPE5{slash}PMD5{slash}RE5-Pad1)") (class "Default")
      (node (ref "U1") (pin "1") (pinfunction "AN17/ETXEN/RPE5/PMD5/RE5_1") (pintype "bidirectional"))
    )
    (net (code "179") (name "unconnected-(U1-AN18{slash}ERXERR{slash}PMD4{slash}RE4-Pad64)") (class "Default")
      (node (ref "U1") (pin "64") (pinfunction "AN18/ERXERR/PMD4/RE4_64") (pintype "bidirectional"))
    )
    (net (code "180") (name "unconnected-(U1-AN45{slash}C1INA{slash}RPB5{slash}RB5-Pad11)") (class "Default")
      (node (ref "U1") (pin "11") (pinfunction "AN45/C1INA/RPB5/RB5_11") (pintype "bidirectional"))
    )
    (net (code "181") (name "unconnected-(U1-AN48{slash}RPB8{slash}PMA10{slash}RB8-Pad21)") (class "Default")
      (node (ref "U1") (pin "21") (pinfunction "AN48/RPB8/PMA10/RB8_21") (pintype "bidirectional"))
    )
    (net (code "182") (name "unconnected-(U1-AN49{slash}RPB9{slash}PMA7{slash}RB9-Pad22)") (class "Default")
      (node (ref "U1") (pin "22") (pinfunction "AN49/RPB9/PMA7/RB9_22") (pintype "bidirectional"))
    )
    (net (code "183") (name "unconnected-(U1-D+-Pad37)") (class "Default")
      (node (ref "U1") (pin "37") (pinfunction "D+_37") (pintype "bidirectional"))
    )
    (net (code "184") (name "unconnected-(U1-D--Pad36)") (class "Default")
      (node (ref "U1") (pin "36") (pinfunction "D-_36") (pintype "bidirectional"))
    )
    (net (code "185") (name "unconnected-(U1-ERXD3{slash}AETXD1{slash}RPF0{slash}RF0-Pad56)") (class "Default")
      (node (ref "U1") (pin "56") (pinfunction "ERXD3/AETXD1/RPF0/RF0_56") (pintype "bidirectional"))
    )
    (net (code "186") (name "unconnected-(U1-OSC1{slash}CLKI{slash}RC12-Pad31)") (class "Default")
      (node (ref "U1") (pin "31") (pinfunction "OSC1/CLKI/RC12_31") (pintype "bidirectional"))
    )
    (net (code "187") (name "unconnected-(U1-OSC2{slash}CLKO{slash}RC15-Pad32)") (class "Default")
      (node (ref "U1") (pin "32") (pinfunction "OSC2/CLKO/RC15_32") (pintype "bidirectional"))
    )
    (net (code "188") (name "unconnected-(U1-PGEC2{slash}AN46{slash}RPB6{slash}RB6-Pad17)") (class "Default")
      (node (ref "U1") (pin "17") (pinfunction "PGEC2/AN46/RPB6/RB6_17") (pintype "bidirectional"))
    )
    (net (code "189") (name "unconnected-(U1-PGED2{slash}AN47{slash}RPB7{slash}RB7-Pad18)") (class "Default")
      (node (ref "U1") (pin "18") (pinfunction "PGED2/AN47/RPB7/RB7_18") (pintype "bidirectional"))
    )
    (net (code "190") (name "unconnected-(U1-RPF3{slash}USBID{slash}RF3-Pad38)") (class "Default")
      (node (ref "U1") (pin "38") (pinfunction "RPF3/USBID/RF3_38") (pintype "bidirectional"))
    )
    (net (code "191") (name "unconnected-(U1-RPF4{slash}SDA5{slash}PMA9{slash}RF4-Pad41)") (class "Default")
      (node (ref "U1") (pin "41") (pinfunction "RPF4/SDA5/PMA9/RF4_41") (pintype "bidirectional"))
    )
    (net (code "192") (name "unconnected-(U1-RPF5{slash}SCL5{slash}PMA8{slash}RF5-Pad42)") (class "Default")
      (node (ref "U1") (pin "42") (pinfunction "RPF5/SCL5/PMA8/RF5_42") (pintype "bidirectional"))
    )
    (net (code "193") (name "unconnected-(U1-SOSCI{slash}RPC13{slash}RC13-Pad47)") (class "Default")
      (node (ref "U1") (pin "47") (pinfunction "SOSCI/RPC13/RC13_47") (pintype "bidirectional"))
    )
    (net (code "194") (name "unconnected-(U1-SOSCO{slash}RPC14{slash}T1CK{slash}RC14-Pad48)") (class "Default")
      (node (ref "U1") (pin "48") (pinfunction "SOSCO/RPC14/T1CK/RC14_48") (pintype "bidirectional"))
    )
    (net (code "195") (name "unconnected-(U1-SQICS0{slash}RPD4{slash}PMWR{slash}RD4-Pad52)") (class "Default")
      (node (ref "U1") (pin "52") (pinfunction "SQICS0/RPD4/PMWR/RD4_52") (pintype "bidirectional"))
    )
    (net (code "196") (name "unconnected-(U1-SQICS1{slash}RPD5{slash}PMRD{slash}RD5-Pad53)") (class "Default")
      (node (ref "U1") (pin "53") (pinfunction "SQICS1/RPD5/PMRD/RD5_53") (pintype "bidirectional"))
    )
    (net (code "197") (name "unconnected-(U1-TCK{slash}AN7{slash}PMA11{slash}RB12-Pad27)") (class "Default")
      (node (ref "U1") (pin "27") (pinfunction "TCK/AN7/PMA11/RB12_27") (pintype "bidirectional"))
    )
    (net (code "198") (name "unconnected-(U1-TDI{slash}AN8{slash}RB13-Pad28)") (class "Default")
      (node (ref "U1") (pin "28") (pinfunction "TDI/AN8/RB13_28") (pintype "bidirectional"))
    )
    (net (code "199") (name "unconnected-(U1-TDO{slash}AN6{slash}PMA12{slash}RB11-Pad24)") (class "Default")
      (node (ref "U1") (pin "24") (pinfunction "TDO/AN6/PMA12/RB11_24") (pintype "bidirectional"))
    )
    (net (code "200") (name "unconnected-(U1-TMS{slash}CVREFOUT{slash}AN5{slash}RPB10{slash}PMA13{slash}RB10-Pad23)") (class "Default")
      (node (ref "U1") (pin "23") (pinfunction "TMS/CVREFOUT/AN5/RPB10/PMA13/RB10_23") (pintype "bidirectional"))
    )
    (net (code "201") (name "unconnected-(U1-TRCLK{slash}SQICLK{slash}ERXD2{slash}AETXD0{slash}RPF1{slash}RF1-Pad57)") (class "Default")
      (node (ref "U1") (pin "57") (pinfunction "TRCLK/SQICLK/ERXD2/AETXD0/RPF1/RF1_57") (pintype "bidirectional"))
    )
    (net (code "202") (name "unconnected-(U1-TRD0{slash}SQID0{slash}ERXD1{slash}PMD0{slash}RE0-Pad58)") (class "Default")
      (node (ref "U1") (pin "58") (pinfunction "TRD0/SQID0/ERXD1/PMD0/RE0_58") (pintype "bidirectional"))
    )
    (net (code "203") (name "unconnected-(U1-TRD1{slash}SQID1{slash}ERXD0{slash}PMD1{slash}RE1-Pad61)") (class "Default")
      (node (ref "U1") (pin "61") (pinfunction "TRD1/SQID1/ERXD0/PMD1/RE1_61") (pintype "bidirectional"))
    )
    (net (code "204") (name "unconnected-(U1-TRD2{slash}SQID2{slash}ERXDV{slash}ECRSDV{slash}AECRSDV{slash}PMD2{slash}RE2-Pad62)") (class "Default")
      (node (ref "U1") (pin "62") (pinfunction "TRD2/SQID2/ERXDV/ECRSDV/AECRSDV/PMD2/RE2_62") (pintype "bidirectional"))
    )
    (net (code "205") (name "unconnected-(U1-TRD3{slash}SQID3{slash}ERXCLK{slash}EREFCLK{slash}RPE3{slash}PMD3{slash}RE3-Pad63)") (class "Default")
      (node (ref "U1") (pin "63") (pinfunction "TRD3/SQID3/ERXCLK/EREFCLK/RPE3/PMD3/RE3_63") (pintype "bidirectional"))
    )
  )
)
